# OBCv4_24.net
KiCad netlist of a schematic drawn in EAGLE
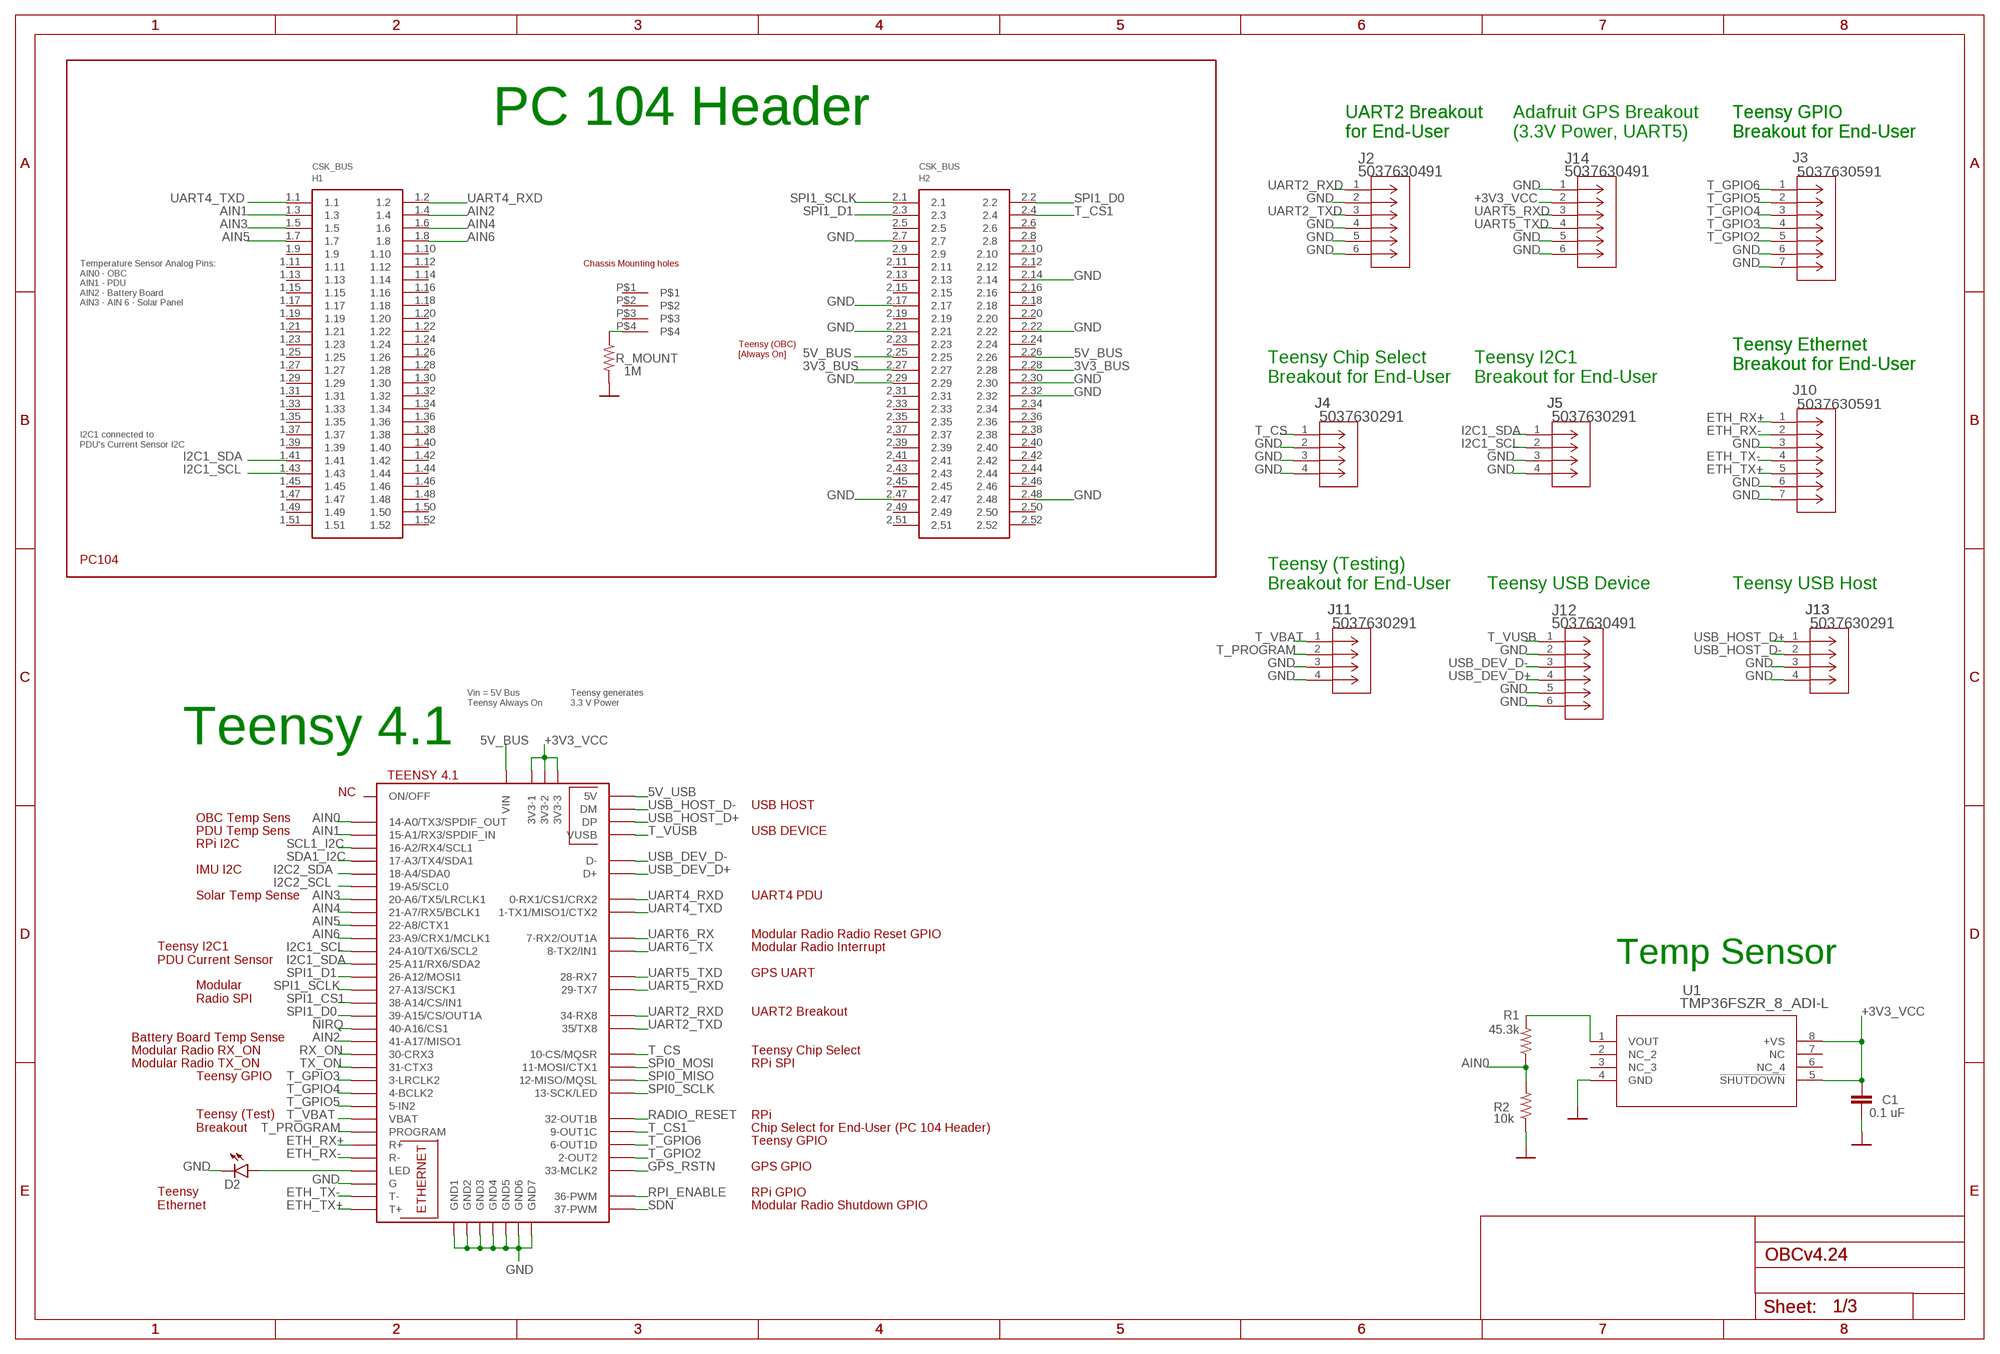
[diagram p0: schematic, sheet 1]
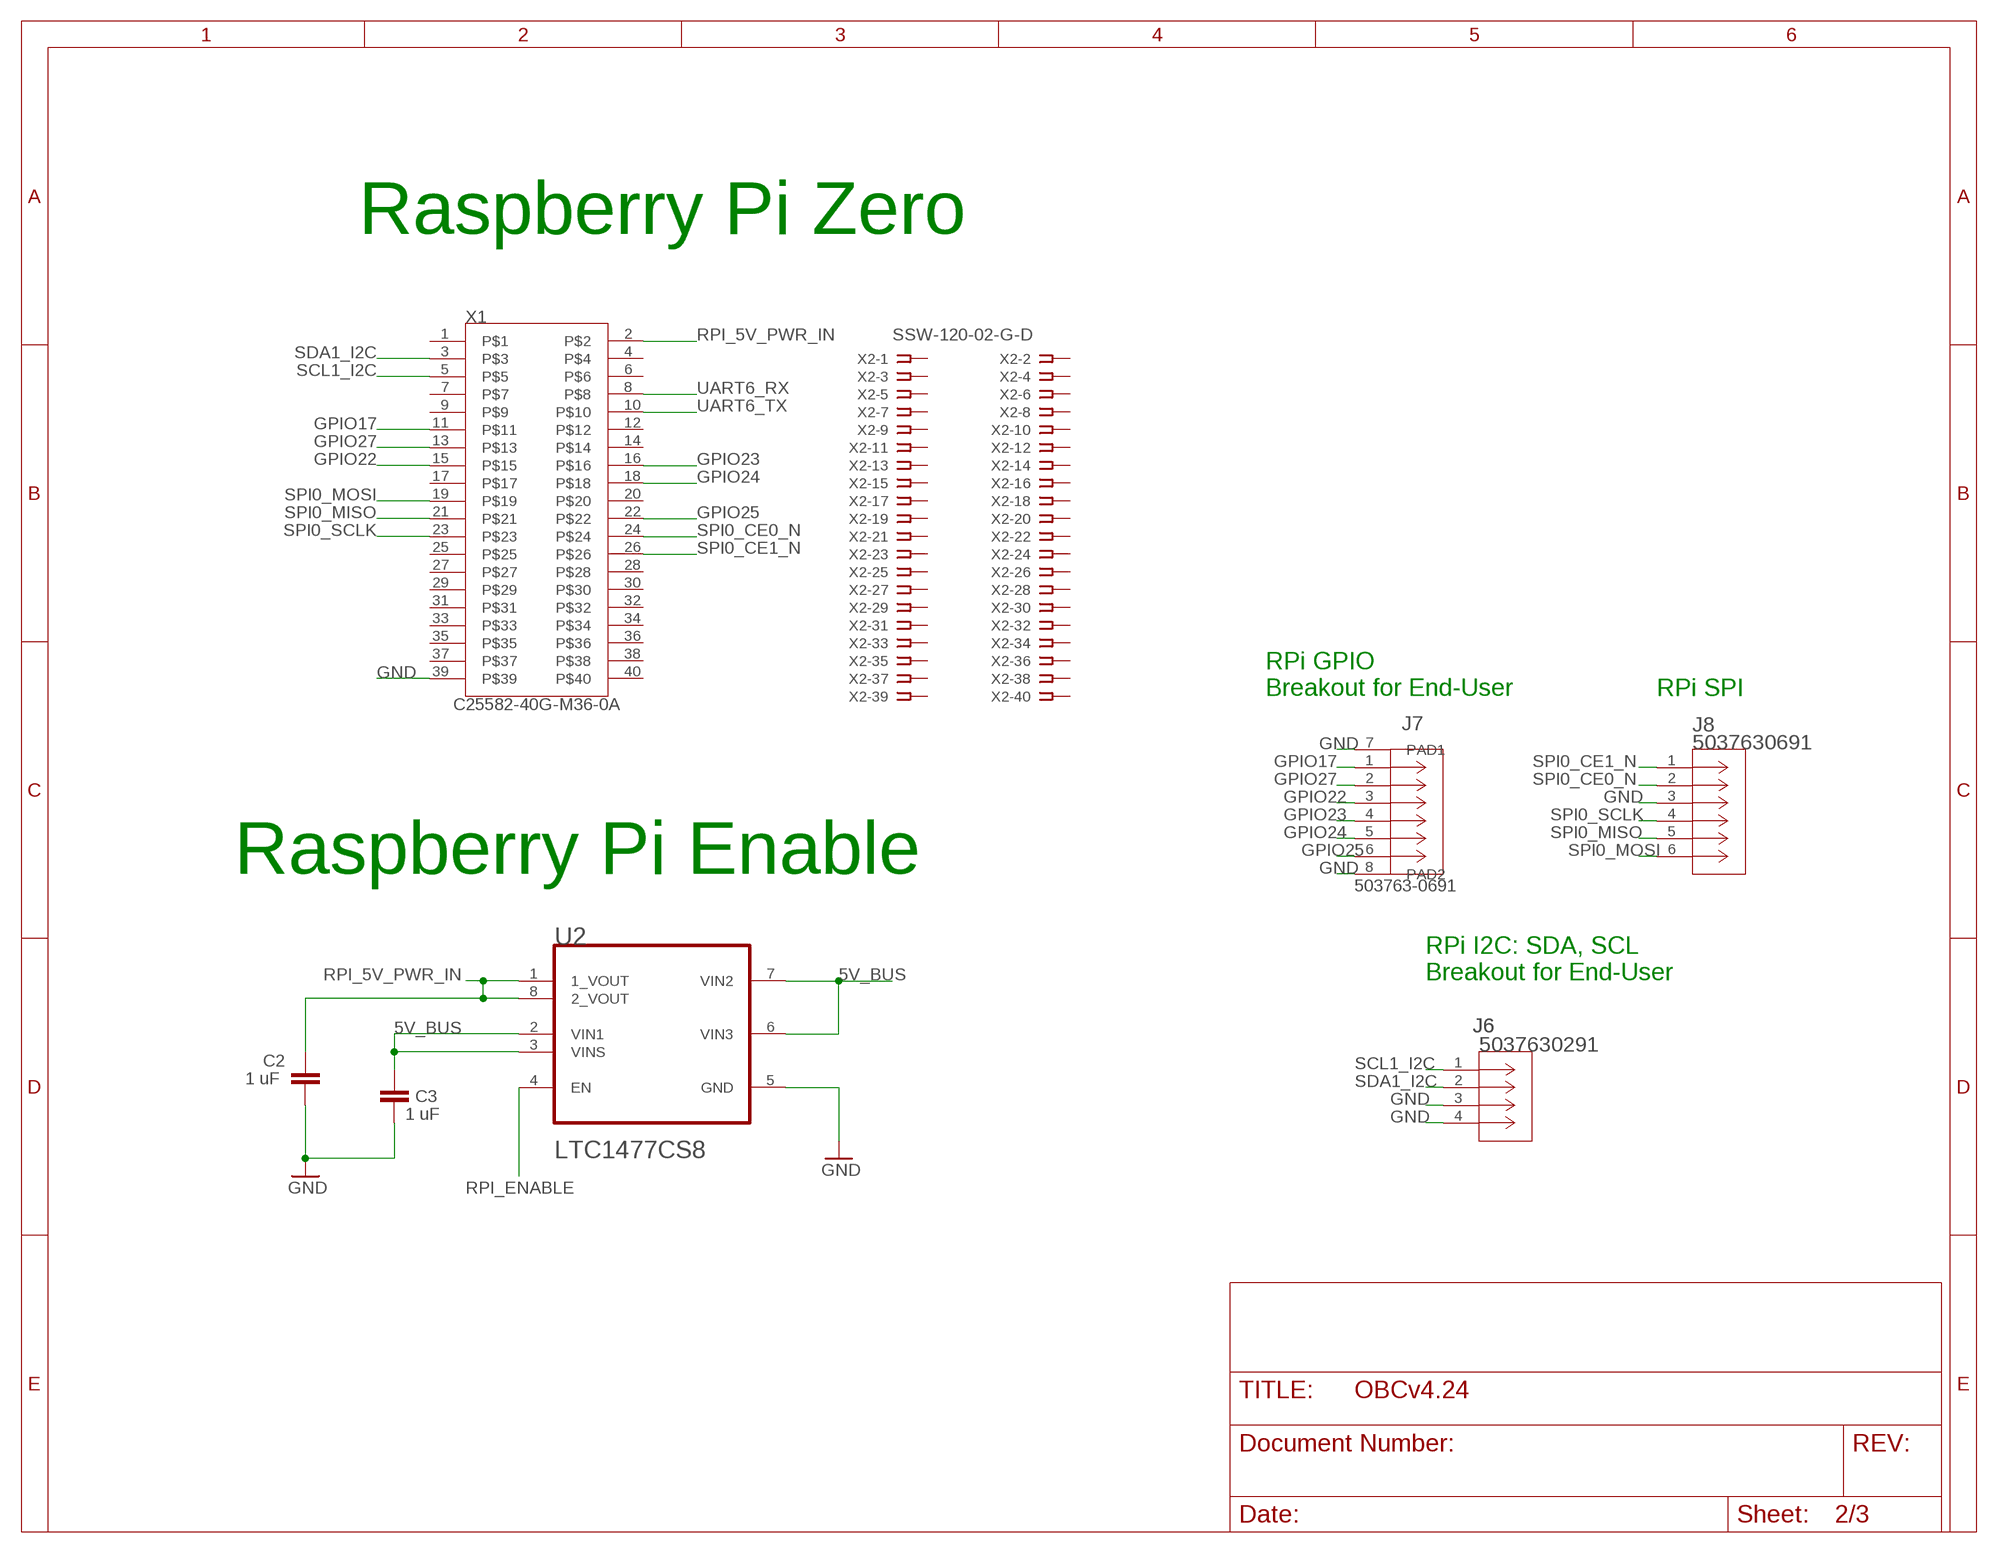
[diagram p1: schematic, sheet 2]
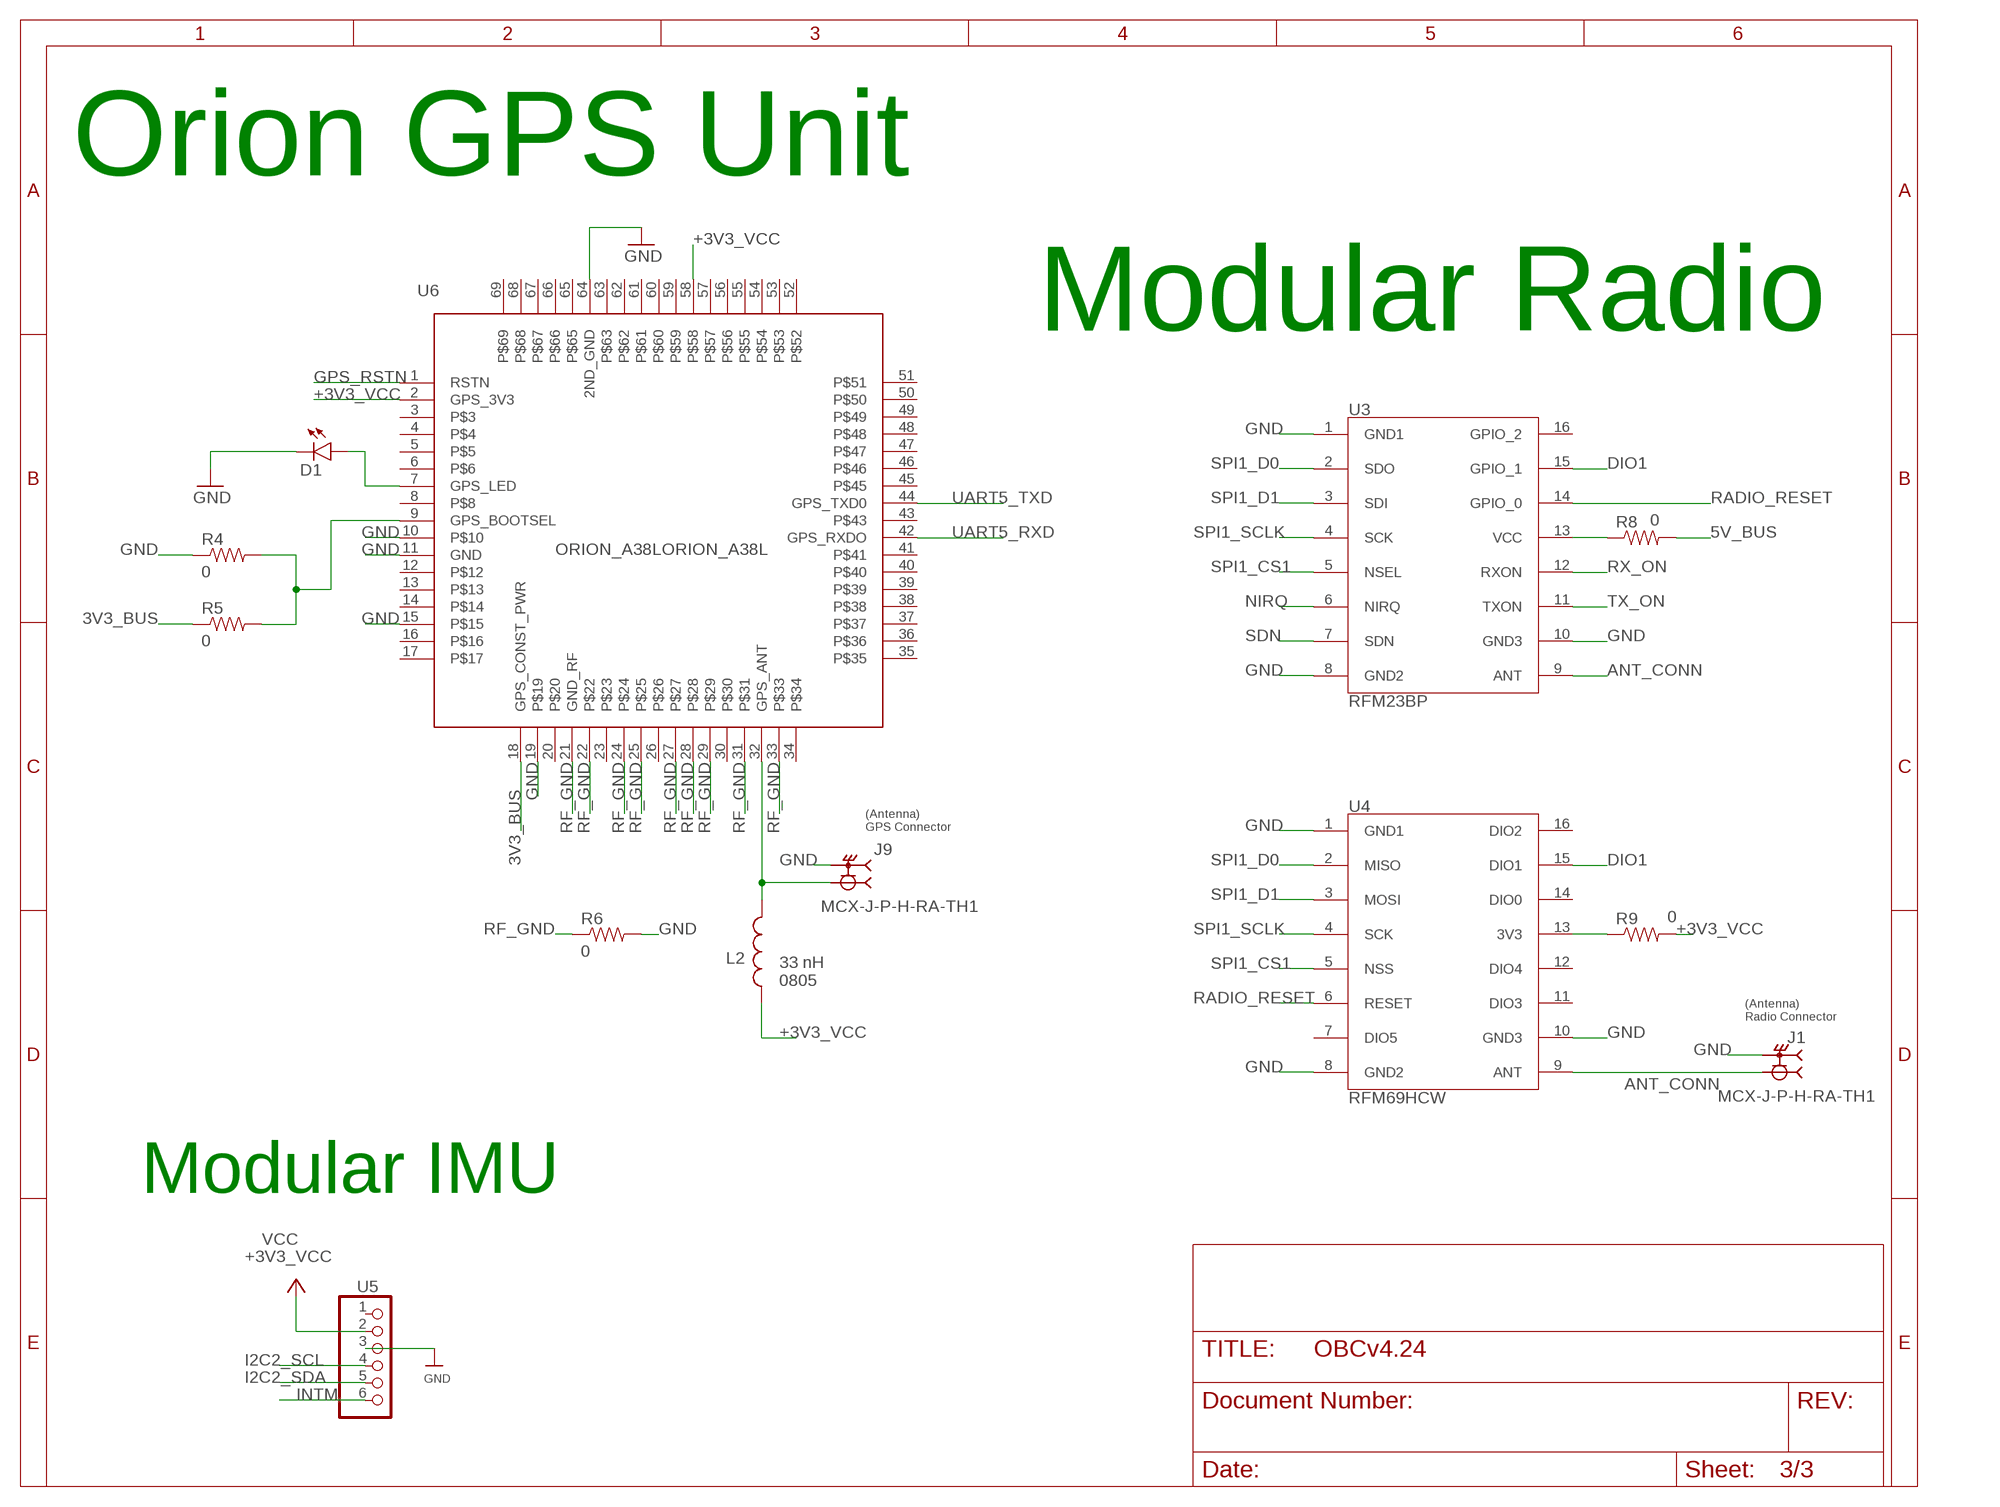
[diagram p2: schematic, sheet 3]

(export (version "E")
  (design (tool "Eeschema 10.0.6"))
  (components
    (comp (ref "C2")
      (value "1 uF")
      (footprint "eagle-import:0805")
      (libsource (lib "eagle-import") (part "CAP0805"))
    )
    (comp (ref "C3")
      (value "1 uF")
      (footprint "eagle-import:0805")
      (libsource (lib "eagle-import") (part "CAP0805"))
    )
    (comp (ref "J6")
      (value "5037630291")
      (footprint "eagle-import:CON_5037630291")
      (fields (field (name "COPYRIGHT") "Copyright (C) 2018 Accelerated Designs. All rights reserved"))
      (libsource (lib "eagle-import") (part "5037630291"))
    )
    (comp (ref "J7")
      (value "503763-0691")
      (footprint "eagle-import:CONN_503763-0691_MOL")
      (fields (field (name "COPYRIGHT") "Copyright (C) 2018 Accelerated Designs. All rights reserved"))
      (libsource (lib "eagle-import") (part "503763-0691"))
    )
    (comp (ref "J8")
      (value "5037630691")
      (footprint "eagle-import:CONN_503763-0691_MOL")
      (fields
        (field (name "MANUFACTURER_PART_NUMBER") "503763-0691")
        (field (name "COPYRIGHT") "Copyright (C) 2018 Accelerated Designs. All rights reserved")
      )
      (libsource (lib "eagle-import") (part "5037630691"))
    )
    (comp (ref "U2")
      (value "LTC1477CS8LINEAR_TECHNOLOGY_LTC1477CS8_0_2")
      (footprint "eagle-import:LINEAR_TECHNOLOGY_LTC1477CS8_2")
      (fields (field (name "MF") "Linear Technology") (field (name "MPN") "LTC1477CS8"))
      (libsource (lib "eagle-import") (part "LTC1477CS8LINEAR_TECHNOLOGY_LTC1477CS8_0_2"))
    )
    (comp (ref "X1")
      (value "C25582-40G-M36-0A")
      (footprint "eagle-import:ADAFRUIT_C25582-40G-M36-0A_0")
      (libsource (lib "eagle-import") (part "C25582-40G-M36-0A"))
    )
    (comp (ref "X2")
      (value "SSW-120-02-G-D")
      (footprint "eagle-import:SSW-120-02-G-D")
      (fields (field (name "MF") "Samtec Inc."))
      (libsource (lib "eagle-import") (part "SSW-120-02-G-D"))
    )
    (comp (ref "D1")
      (value "LEDCHIP-LED0603")
      (footprint "eagle-import:CHIP-LED0603")
      (libsource (lib "eagle-import") (part "LEDCHIP-LED0603"))
    )
    (comp (ref "J1")
      (value "MCX-J-P-H-RA-TH1")
      (footprint "eagle-import:SAMTEC_MCX-J-P-H-RA-TH1")
      (fields (field (name "DIGI-KEY_PART_NUMBER") "SAM10607-ND") (field (name "MF") "Samtec"))
      (libsource (lib "eagle-import") (part "MCX-J-P-H-RA-TH1"))
    )
    (comp (ref "J9")
      (value "MCX-J-P-H-RA-TH1")
      (footprint "eagle-import:SAMTEC_MCX-J-P-H-RA-TH1")
      (fields (field (name "DIGI-KEY_PART_NUMBER") "SAM10607-ND") (field (name "MF") "Samtec"))
      (libsource (lib "eagle-import") (part "MCX-J-P-H-RA-TH1"))
    )
    (comp (ref "L2")
      (value "AIMC-0805-2N2S-T")
      (footprint "eagle-import:INDC2012X105N")
      (fields (field (name "DIGI-KEY_PART_NUMBER") "535-11562-1-ND") (field (name "MF") "Abracon"))
      (libsource (lib "eagle-import") (part "AIMC-0805-2N2S-T"))
    )
    (comp (ref "R4")
      (value "0")
      (footprint "eagle-import:0805")
      (libsource (lib "eagle-import") (part "RESISTOR0805-RES"))
    )
    (comp (ref "R5")
      (value "0")
      (footprint "eagle-import:0805")
      (libsource (lib "eagle-import") (part "RESISTOR0805-RES"))
    )
    (comp (ref "R6")
      (value "0")
      (footprint "eagle-import:0805")
      (libsource (lib "eagle-import") (part "RESISTOR0805-RES"))
    )
    (comp (ref "R8")
      (value "0")
      (footprint "eagle-import:R2512")
      (libsource (lib "eagle-import") (part "RESISTOR2512"))
    )
    (comp (ref "R9")
      (value "0")
      (footprint "eagle-import:R2512")
      (libsource (lib "eagle-import") (part "RESISTOR2512"))
    )
    (comp (ref "U3")
      (value "RFM23BP")
      (footprint "eagle-import:RFM23BP")
      (libsource (lib "eagle-import") (part "RFM23BP"))
    )
    (comp (ref "U4")
      (value "RFM69HCW")
      (footprint "eagle-import:RFM69HCW")
      (libsource (lib "eagle-import") (part "RFM69HCW"))
    )
    (comp (ref "U5")
      (value "HEADER-1X670MIL")
      (footprint "eagle-import:1X06_ROUND_70")
      (libsource (lib "eagle-import") (part "HEADER-1X670MIL"))
    )
    (comp (ref "U6")
      (value "ORION_A38LORION_A38L")
      (footprint "eagle-import:ORION_A38L")
      (libsource (lib "eagle-import") (part "ORION_A38LORION_A38L"))
    )
    (comp (ref "C1")
      (value "0.1 uF")
      (footprint "eagle-import:0805")
      (libsource (lib "eagle-import") (part "CAP0805"))
    )
    (comp (ref "D2")
      (value "LEDCHIP-LED0603")
      (footprint "eagle-import:CHIP-LED0603")
      (libsource (lib "eagle-import") (part "LEDCHIP-LED0603"))
    )
    (comp (ref "H1")
      (value "PC104_WCONN")
      (footprint "eagle-import:PC104_WCONN")
      (libsource (lib "eagle-import") (part "PC104_WCONN"))
    )
    (comp (ref "J2")
      (value "5037630491")
      (footprint "eagle-import:CON_5037630491")
      (fields (field (name "COPYRIGHT") "Copyright (C) 2018 Accelerated Designs. All rights reserved"))
      (libsource (lib "eagle-import") (part "5037630491"))
    )
    (comp (ref "J3")
      (value "5037630591")
      (footprint "eagle-import:CON_5037630591")
      (fields (field (name "COPYRIGHT") "Copyright (C) 2021 Ultra Librarian. All rights reserved."))
      (libsource (lib "eagle-import") (part "5037630591"))
    )
    (comp (ref "J4")
      (value "5037630291")
      (footprint "eagle-import:CON_5037630291")
      (fields (field (name "COPYRIGHT") "Copyright (C) 2018 Accelerated Designs. All rights reserved"))
      (libsource (lib "eagle-import") (part "5037630291"))
    )
    (comp (ref "J5")
      (value "5037630291")
      (footprint "eagle-import:CON_5037630291")
      (fields (field (name "COPYRIGHT") "Copyright (C) 2018 Accelerated Designs. All rights reserved"))
      (libsource (lib "eagle-import") (part "5037630291"))
    )
    (comp (ref "J10")
      (value "5037630591")
      (footprint "eagle-import:CON_5037630591")
      (fields (field (name "COPYRIGHT") "Copyright (C) 2021 Ultra Librarian. All rights reserved."))
      (libsource (lib "eagle-import") (part "5037630591"))
    )
    (comp (ref "J11")
      (value "5037630291")
      (footprint "eagle-import:CON_5037630291")
      (fields (field (name "COPYRIGHT") "Copyright (C) 2018 Accelerated Designs. All rights reserved"))
      (libsource (lib "eagle-import") (part "5037630291"))
    )
    (comp (ref "J12")
      (value "5037630491")
      (footprint "eagle-import:CON_5037630491")
      (fields (field (name "COPYRIGHT") "Copyright (C) 2018 Accelerated Designs. All rights reserved"))
      (libsource (lib "eagle-import") (part "5037630491"))
    )
    (comp (ref "J13")
      (value "5037630291")
      (footprint "eagle-import:CON_5037630291")
      (fields (field (name "COPYRIGHT") "Copyright (C) 2018 Accelerated Designs. All rights reserved"))
      (libsource (lib "eagle-import") (part "5037630291"))
    )
    (comp (ref "J14")
      (value "5037630491")
      (footprint "eagle-import:CON_5037630491")
      (fields (field (name "COPYRIGHT") "Copyright (C) 2018 Accelerated Designs. All rights reserved"))
      (libsource (lib "eagle-import") (part "5037630491"))
    )
    (comp (ref "R1")
      (value "45.3k")
      (footprint "eagle-import:0805")
      (libsource (lib "eagle-import") (part "RESISTOR0805-RES"))
    )
    (comp (ref "R2")
      (value "10k")
      (footprint "eagle-import:0805")
      (libsource (lib "eagle-import") (part "RESISTOR0805-RES"))
    )
    (comp (ref "R_MOUNT")
      (value "1M")
      (footprint "eagle-import:0805")
      (libsource (lib "eagle-import") (part "RESISTOR0805-RES"))
    )
    (comp (ref "U$1")
      (value "TEENSY41TEENSY")
      (footprint "eagle-import:TEENSY41")
      (libsource (lib "eagle-import") (part "TEENSY41TEENSY"))
    )
    (comp (ref "U1")
      (value "TMP36FSZR_8_ADI-L")
      (footprint "eagle-import:R_8_ADI-L")
      (fields
        (field (name "MANUFACTURER_PART_NUMBER") "TMP36FSZ")
        (field (name "COPYRIGHT") "Copyright (C) 2021 Ultra Librarian. All rights reserved.")
      )
      (libsource (lib "eagle-import") (part "TMP36FSZR_8_ADI-L"))
    )
  )
  (nets
    (net (code "1") (name "+3V3_VCC") (class "Default")
      (node (ref "C1") (pin "1") (pinfunction "1_1") (pintype "passive"))
      (node (ref "J14") (pin "2") (pinfunction "2_2") (pintype "passive"))
      (node (ref "L2") (pin "1") (pinfunction "1_1") (pintype "passive"))
      (node (ref "R9") (pin "2") (pinfunction "2_2") (pintype "passive"))
      (node (ref "U$1") (pin "3V3-1") (pinfunction "3V3-1_3V3-1") (pintype "bidirectional"))
      (node (ref "U$1") (pin "3V3-2") (pinfunction "3V3-2_3V3-2") (pintype "bidirectional"))
      (node (ref "U$1") (pin "3V3-3") (pinfunction "3V3-3_3V3-3") (pintype "bidirectional"))
      (node (ref "U1") (pin "5") (pinfunction "~{SHUTDOWN}_5") (pintype "passive"))
      (node (ref "U1") (pin "8") (pinfunction "+VS_8") (pintype "power_in"))
      (node (ref "U5") (pin "2") (pinfunction "2_2") (pintype "passive"))
      (node (ref "U6") (pin "2") (pinfunction "GPS_3V3_2") (pintype "bidirectional"))
      (node (ref "U6") (pin "58") (pinfunction "P$58_58") (pintype "bidirectional"))
    )
    (net (code "2") (name "3V3_BUS") (class "Default")
      (node (ref "H1") (pin "2.27") (pinfunction "2.27_2.27") (pintype "bidirectional"))
      (node (ref "H1") (pin "2.28") (pinfunction "2.28_2.28") (pintype "bidirectional"))
      (node (ref "R5") (pin "1") (pinfunction "1_1") (pintype "passive"))
      (node (ref "U6") (pin "18") (pinfunction "GPS_CONST_PWR_18") (pintype "bidirectional"))
    )
    (net (code "3") (name "5V_BUS") (class "Default")
      (node (ref "C3") (pin "1") (pinfunction "1_1") (pintype "passive"))
      (node (ref "H1") (pin "2.25") (pinfunction "2.25_2.25") (pintype "bidirectional"))
      (node (ref "H1") (pin "2.26") (pinfunction "2.26_2.26") (pintype "bidirectional"))
      (node (ref "R8") (pin "2") (pinfunction "2_2") (pintype "passive"))
      (node (ref "U$1") (pin "VIN") (pinfunction "VIN_VIN") (pintype "bidirectional"))
      (node (ref "U2") (pin "2") (pinfunction "VIN1_2") (pintype "power_in"))
      (node (ref "U2") (pin "3") (pinfunction "VINS_3") (pintype "power_in"))
      (node (ref "U2") (pin "6") (pinfunction "VIN3_6") (pintype "power_in"))
      (node (ref "U2") (pin "7") (pinfunction "VIN2_7") (pintype "power_in"))
    )
    (net (code "4") (name "5V_USB") (class "Default")
      (node (ref "U$1") (pin "+5V") (pinfunction "5V_+5V") (pintype "bidirectional"))
    )
    (net (code "5") (name "AIN0") (class "Default")
      (node (ref "R1") (pin "1") (pinfunction "1_1") (pintype "passive"))
      (node (ref "R2") (pin "2") (pinfunction "2_2") (pintype "passive"))
      (node (ref "U$1") (pin "14-A0/TX3/SPDIF_OUT") (pinfunction "14-A0/TX3/SPDIF_OUT_14-A0/TX3/SPDIF_OUT") (pintype "bidirectional"))
    )
    (net (code "6") (name "AIN1") (class "Default")
      (node (ref "H1") (pin "1.3") (pinfunction "1.3_1.3") (pintype "bidirectional"))
      (node (ref "U$1") (pin "15-A1/RX3/SPDIF_IN") (pinfunction "15-A1/RX3/SPDIF_IN_15-A1/RX3/SPDIF_IN") (pintype "bidirectional"))
    )
    (net (code "7") (name "AIN2") (class "Default")
      (node (ref "H1") (pin "1.4") (pinfunction "1.4_1.4") (pintype "bidirectional"))
      (node (ref "U$1") (pin "41-A17/MISO1") (pinfunction "41-A17/MISO1_41-A17/MISO1") (pintype "bidirectional"))
    )
    (net (code "8") (name "AIN3") (class "Default")
      (node (ref "H1") (pin "1.5") (pinfunction "1.5_1.5") (pintype "bidirectional"))
      (node (ref "U$1") (pin "20-A6/TX5/LRCLK1") (pinfunction "20-A6/TX5/LRCLK1_20-A6/TX5/LRCLK1") (pintype "bidirectional"))
    )
    (net (code "9") (name "AIN4") (class "Default")
      (node (ref "H1") (pin "1.6") (pinfunction "1.6_1.6") (pintype "bidirectional"))
      (node (ref "U$1") (pin "21-A7/RX5/BCLK1") (pinfunction "21-A7/RX5/BCLK1_21-A7/RX5/BCLK1") (pintype "bidirectional"))
    )
    (net (code "10") (name "AIN5") (class "Default")
      (node (ref "H1") (pin "1.7") (pinfunction "1.7_1.7") (pintype "bidirectional"))
      (node (ref "U$1") (pin "22-A8/CTX1") (pinfunction "22-A8/CTX1_22-A8/CTX1") (pintype "bidirectional"))
    )
    (net (code "11") (name "AIN6") (class "Default")
      (node (ref "H1") (pin "1.8") (pinfunction "1.8_1.8") (pintype "bidirectional"))
      (node (ref "U$1") (pin "23-A9/CRX1/MCLK1") (pinfunction "23-A9/CRX1/MCLK1_23-A9/CRX1/MCLK1") (pintype "bidirectional"))
    )
    (net (code "12") (name "ANT_CONN") (class "Default")
      (node (ref "J1") (pin "1") (pinfunction "1_1") (pintype "passive"))
      (node (ref "U3") (pin "9") (pinfunction "ANT_9") (pintype "bidirectional"))
      (node (ref "U4") (pin "9") (pinfunction "ANT_9") (pintype "bidirectional"))
    )
    (net (code "13") (name "DIO1") (class "Default")
      (node (ref "U3") (pin "15") (pinfunction "GPIO_1_15") (pintype "bidirectional"))
      (node (ref "U4") (pin "15") (pinfunction "DIO1_15") (pintype "bidirectional"))
    )
    (net (code "14") (name "ETH_RX+") (class "Default")
      (node (ref "J10") (pin "1") (pinfunction "1_1") (pintype "passive"))
      (node (ref "U$1") (pin "R+") (pinfunction "R+_R+") (pintype "bidirectional"))
    )
    (net (code "15") (name "ETH_RX-") (class "Default")
      (node (ref "J10") (pin "2") (pinfunction "2_2") (pintype "passive"))
      (node (ref "U$1") (pin "R-") (pinfunction "R-_R-") (pintype "bidirectional"))
    )
    (net (code "16") (name "ETH_TX+") (class "Default")
      (node (ref "J10") (pin "5") (pinfunction "5_5") (pintype "passive"))
      (node (ref "U$1") (pin "T+") (pinfunction "T+_T+") (pintype "bidirectional"))
    )
    (net (code "17") (name "ETH_TX-") (class "Default")
      (node (ref "J10") (pin "4") (pinfunction "4_4") (pintype "passive"))
      (node (ref "U$1") (pin "T-") (pinfunction "T-_T-") (pintype "bidirectional"))
    )
    (net (code "18") (name "GND") (class "Default")
      (node (ref "C1") (pin "2") (pinfunction "2_2") (pintype "passive"))
      (node (ref "C2") (pin "2") (pinfunction "2_2") (pintype "passive"))
      (node (ref "C3") (pin "2") (pinfunction "2_2") (pintype "passive"))
      (node (ref "D1") (pin "C") (pinfunction "C_C") (pintype "passive"))
      (node (ref "D2") (pin "C") (pinfunction "C_C") (pintype "passive"))
      (node (ref "H1") (pin "2.14") (pinfunction "2.14_2.14") (pintype "bidirectional"))
      (node (ref "H1") (pin "2.17") (pinfunction "2.17_2.17") (pintype "bidirectional"))
      (node (ref "H1") (pin "2.21") (pinfunction "2.21_2.21") (pintype "bidirectional"))
      (node (ref "H1") (pin "2.22") (pinfunction "2.22_2.22") (pintype "bidirectional"))
      (node (ref "H1") (pin "2.29") (pinfunction "2.29_2.29") (pintype "bidirectional"))
      (node (ref "H1") (pin "2.30") (pinfunction "2.30_2.30") (pintype "bidirectional"))
      (node (ref "H1") (pin "2.32") (pinfunction "2.32_2.32") (pintype "bidirectional"))
      (node (ref "H1") (pin "2.47") (pinfunction "2.47_2.47") (pintype "bidirectional"))
      (node (ref "H1") (pin "2.48") (pinfunction "2.48_2.48") (pintype "bidirectional"))
      (node (ref "H1") (pin "2.7") (pinfunction "2.7_2.7") (pintype "bidirectional"))
      (node (ref "J1") (pin "S1") (pinfunction "2_S1") (pintype "passive"))
      (node (ref "J1") (pin "S2") (pinfunction "2_S2") (pintype "passive"))
      (node (ref "J1") (pin "S3") (pinfunction "2_S3") (pintype "passive"))
      (node (ref "J1") (pin "S4") (pinfunction "2_S4") (pintype "passive"))
      (node (ref "J10") (pin "3") (pinfunction "3_3") (pintype "passive"))
      (node (ref "J10") (pin "6") (pinfunction "6_6") (pintype "passive"))
      (node (ref "J10") (pin "7") (pinfunction "7_7") (pintype "passive"))
      (node (ref "J11") (pin "3") (pinfunction "3_3") (pintype "passive"))
      (node (ref "J11") (pin "4") (pinfunction "4_4") (pintype "passive"))
      (node (ref "J12") (pin "2") (pinfunction "2_2") (pintype "passive"))
      (node (ref "J12") (pin "5") (pinfunction "5_5") (pintype "passive"))
      (node (ref "J12") (pin "6") (pinfunction "6_6") (pintype "passive"))
      (node (ref "J13") (pin "3") (pinfunction "3_3") (pintype "passive"))
      (node (ref "J13") (pin "4") (pinfunction "4_4") (pintype "passive"))
      (node (ref "J14") (pin "1") (pinfunction "1_1") (pintype "passive"))
      (node (ref "J14") (pin "5") (pinfunction "5_5") (pintype "passive"))
      (node (ref "J14") (pin "6") (pinfunction "6_6") (pintype "passive"))
      (node (ref "J2") (pin "2") (pinfunction "2_2") (pintype "passive"))
      (node (ref "J2") (pin "4") (pinfunction "4_4") (pintype "passive"))
      (node (ref "J2") (pin "5") (pinfunction "5_5") (pintype "passive"))
      (node (ref "J2") (pin "6") (pinfunction "6_6") (pintype "passive"))
      (node (ref "J3") (pin "6") (pinfunction "6_6") (pintype "passive"))
      (node (ref "J3") (pin "7") (pinfunction "7_7") (pintype "passive"))
      (node (ref "J4") (pin "2") (pinfunction "2_2") (pintype "passive"))
      (node (ref "J4") (pin "3") (pinfunction "3_3") (pintype "passive"))
      (node (ref "J4") (pin "4") (pinfunction "4_4") (pintype "passive"))
      (node (ref "J5") (pin "3") (pinfunction "3_3") (pintype "passive"))
      (node (ref "J5") (pin "4") (pinfunction "4_4") (pintype "passive"))
      (node (ref "J6") (pin "3") (pinfunction "3_3") (pintype "passive"))
      (node (ref "J6") (pin "4") (pinfunction "4_4") (pintype "passive"))
      (node (ref "J7") (pin "7") (pinfunction "PAD1_7") (pintype "bidirectional"))
      (node (ref "J7") (pin "8") (pinfunction "PAD2_8") (pintype "bidirectional"))
      (node (ref "J8") (pin "3") (pinfunction "3_3") (pintype "passive"))
      (node (ref "J9") (pin "S1") (pinfunction "2_S1") (pintype "passive"))
      (node (ref "J9") (pin "S2") (pinfunction "2_S2") (pintype "passive"))
      (node (ref "J9") (pin "S3") (pinfunction "2_S3") (pintype "passive"))
      (node (ref "J9") (pin "S4") (pinfunction "2_S4") (pintype "passive"))
      (node (ref "R2") (pin "1") (pinfunction "1_1") (pintype "passive"))
      (node (ref "R4") (pin "1") (pinfunction "1_1") (pintype "passive"))
      (node (ref "R6") (pin "2") (pinfunction "2_2") (pintype "passive"))
      (node (ref "R_MOUNT") (pin "2") (pinfunction "2_2") (pintype "passive"))
      (node (ref "U$1") (pin "G") (pinfunction "G_G") (pintype "bidirectional"))
      (node (ref "U$1") (pin "GND") (pinfunction "GND7_GND") (pintype "bidirectional"))
      (node (ref "U$1") (pin "GND1") (pinfunction "GND1_GND1") (pintype "bidirectional"))
      (node (ref "U$1") (pin "GND2") (pinfunction "GND2_GND2") (pintype "bidirectional"))
      (node (ref "U$1") (pin "GND3") (pinfunction "GND3_GND3") (pintype "bidirectional"))
      (node (ref "U$1") (pin "GND4") (pinfunction "GND4_GND4") (pintype "bidirectional"))
      (node (ref "U$1") (pin "GND5") (pinfunction "GND5_GND5") (pintype "bidirectional"))
      (node (ref "U$1") (pin "GND6") (pinfunction "GND6_GND6") (pintype "bidirectional"))
      (node (ref "U1") (pin "4") (pinfunction "GND_4") (pintype "passive"))
      (node (ref "U2") (pin "5") (pinfunction "GND_5") (pintype "power_in"))
      (node (ref "U3") (pin "1") (pinfunction "GND1_1") (pintype "bidirectional"))
      (node (ref "U3") (pin "10") (pinfunction "GND3_10") (pintype "bidirectional"))
      (node (ref "U3") (pin "8") (pinfunction "GND2_8") (pintype "bidirectional"))
      (node (ref "U4") (pin "1") (pinfunction "GND1_1") (pintype "bidirectional"))
      (node (ref "U4") (pin "10") (pinfunction "GND3_10") (pintype "bidirectional"))
      (node (ref "U4") (pin "8") (pinfunction "GND2_8") (pintype "bidirectional"))
      (node (ref "U5") (pin "3") (pinfunction "3_3") (pintype "passive"))
      (node (ref "U6") (pin "10") (pinfunction "P$10_10") (pintype "bidirectional"))
      (node (ref "U6") (pin "11") (pinfunction "GND_11") (pintype "bidirectional"))
      (node (ref "U6") (pin "15") (pinfunction "P$15_15") (pintype "bidirectional"))
      (node (ref "U6") (pin "19") (pinfunction "P$19_19") (pintype "bidirectional"))
      (node (ref "U6") (pin "64") (pinfunction "2ND_GND_64") (pintype "bidirectional"))
      (node (ref "X1") (pin "39") (pinfunction "P$39_39") (pintype "bidirectional"))
    )
    (net (code "19") (name "GPIO17") (class "Default")
      (node (ref "J7") (pin "1") (pinfunction "1_1") (pintype "passive"))
      (node (ref "X1") (pin "11") (pinfunction "P$11_11") (pintype "bidirectional"))
    )
    (net (code "20") (name "GPIO22") (class "Default")
      (node (ref "J7") (pin "3") (pinfunction "3_3") (pintype "passive"))
      (node (ref "X1") (pin "15") (pinfunction "P$15_15") (pintype "bidirectional"))
    )
    (net (code "21") (name "GPIO23") (class "Default")
      (node (ref "J7") (pin "4") (pinfunction "4_4") (pintype "passive"))
      (node (ref "X1") (pin "16") (pinfunction "P$16_16") (pintype "bidirectional"))
    )
    (net (code "22") (name "GPIO24") (class "Default")
      (node (ref "J7") (pin "5") (pinfunction "5_5") (pintype "passive"))
      (node (ref "X1") (pin "18") (pinfunction "P$18_18") (pintype "bidirectional"))
    )
    (net (code "23") (name "GPIO25") (class "Default")
      (node (ref "J7") (pin "6") (pinfunction "6_6") (pintype "passive"))
      (node (ref "X1") (pin "22") (pinfunction "P$22_22") (pintype "bidirectional"))
    )
    (net (code "24") (name "GPIO27") (class "Default")
      (node (ref "J7") (pin "2") (pinfunction "2_2") (pintype "passive"))
      (node (ref "X1") (pin "13") (pinfunction "P$13_13") (pintype "bidirectional"))
    )
    (net (code "25") (name "GPS_RSTN") (class "Default")
      (node (ref "U$1") (pin "33-MCLK2") (pinfunction "33-MCLK2_33-MCLK2") (pintype "bidirectional"))
      (node (ref "U6") (pin "1") (pinfunction "RSTN_1") (pintype "bidirectional"))
    )
    (net (code "26") (name "I2C1_SCL") (class "Default")
      (node (ref "H1") (pin "1.43") (pinfunction "1.43_1.43") (pintype "bidirectional"))
      (node (ref "J5") (pin "2") (pinfunction "2_2") (pintype "passive"))
      (node (ref "U$1") (pin "24-A10/TX6/SCL2") (pinfunction "24-A10/TX6/SCL2_24-A10/TX6/SCL2") (pintype "bidirectional"))
    )
    (net (code "27") (name "I2C1_SDA") (class "Default")
      (node (ref "H1") (pin "1.41") (pinfunction "1.41_1.41") (pintype "bidirectional"))
      (node (ref "J5") (pin "1") (pinfunction "1_1") (pintype "passive"))
      (node (ref "U$1") (pin "25-A11/RX6/SDA2") (pinfunction "25-A11/RX6/SDA2_25-A11/RX6/SDA2") (pintype "bidirectional"))
    )
    (net (code "28") (name "I2C2_SCL") (class "Default")
      (node (ref "U$1") (pin "19-A5/SCL0") (pinfunction "19-A5/SCL0_19-A5/SCL0") (pintype "bidirectional"))
      (node (ref "U5") (pin "4") (pinfunction "4_4") (pintype "passive"))
    )
    (net (code "29") (name "I2C2_SDA") (class "Default")
      (node (ref "U$1") (pin "18-A4/SDA0") (pinfunction "18-A4/SDA0_18-A4/SDA0") (pintype "bidirectional"))
      (node (ref "U5") (pin "5") (pinfunction "5_5") (pintype "passive"))
    )
    (net (code "30") (name "INTM") (class "Default")
      (node (ref "U5") (pin "6") (pinfunction "6_6") (pintype "passive"))
    )
    (net (code "31") (name "NIRQ") (class "Default")
      (node (ref "U$1") (pin "40-A16/CS1") (pinfunction "40-A16/CS1_40-A16/CS1") (pintype "bidirectional"))
      (node (ref "U3") (pin "6") (pinfunction "NIRQ_6") (pintype "bidirectional"))
    )
    (net (code "32") (name "Net-(D2-PadA)") (class "Default")
      (node (ref "D2") (pin "A") (pinfunction "A_A") (pintype "passive"))
      (node (ref "U$1") (pin "LED") (pinfunction "LED_LED") (pintype "bidirectional"))
    )
    (net (code "33") (name "Net-(H1-PadP$4)") (class "Default")
      (node (ref "H1") (pin "P$4") (pinfunction "P$4_P$4") (pintype "bidirectional"))
      (node (ref "R_MOUNT") (pin "1") (pinfunction "1_1") (pintype "passive"))
    )
    (net (code "34") (name "Net-(U1-VOUT)") (class "Default")
      (node (ref "R1") (pin "2") (pinfunction "2_2") (pintype "passive"))
      (node (ref "U1") (pin "1") (pinfunction "VOUT_1") (pintype "output"))
    )
    (net (code "35") (name "Net-(U3-VCC)") (class "Default")
      (node (ref "R8") (pin "1") (pinfunction "1_1") (pintype "passive"))
      (node (ref "U3") (pin "13") (pinfunction "VCC_13") (pintype "bidirectional"))
    )
    (net (code "36") (name "Net-(U4-3V3)") (class "Default")
      (node (ref "R9") (pin "1") (pinfunction "1_1") (pintype "passive"))
      (node (ref "U4") (pin "13") (pinfunction "3V3_13") (pintype "bidirectional"))
    )
    (net (code "37") (name "Net-(U6-GPS_ANT)") (class "Default")
      (node (ref "J9") (pin "1") (pinfunction "1_1") (pintype "passive"))
      (node (ref "L2") (pin "2") (pinfunction "2_2") (pintype "passive"))
      (node (ref "U6") (pin "32") (pinfunction "GPS_ANT_32") (pintype "bidirectional"))
    )
    (net (code "38") (name "Net-(U6-GPS_BOOTSEL)") (class "Default")
      (node (ref "R4") (pin "2") (pinfunction "2_2") (pintype "passive"))
      (node (ref "R5") (pin "2") (pinfunction "2_2") (pintype "passive"))
      (node (ref "U6") (pin "9") (pinfunction "GPS_BOOTSEL_9") (pintype "bidirectional"))
    )
    (net (code "39") (name "Net-(U6-GPS_LED)") (class "Default")
      (node (ref "D1") (pin "A") (pinfunction "A_A") (pintype "passive"))
      (node (ref "U6") (pin "7") (pinfunction "GPS_LED_7") (pintype "bidirectional"))
    )
    (net (code "40") (name "RADIO_RESET") (class "Default")
      (node (ref "U$1") (pin "32-OUT1B") (pinfunction "32-OUT1B_32-OUT1B") (pintype "bidirectional"))
      (node (ref "U3") (pin "14") (pinfunction "GPIO_0_14") (pintype "bidirectional"))
      (node (ref "U4") (pin "6") (pinfunction "RESET_6") (pintype "bidirectional"))
    )
    (net (code "41") (name "RF_GND") (class "Default")
      (node (ref "R6") (pin "1") (pinfunction "1_1") (pintype "passive"))
      (node (ref "U6") (pin "21") (pinfunction "GND_RF_21") (pintype "bidirectional"))
      (node (ref "U6") (pin "22") (pinfunction "P$22_22") (pintype "bidirectional"))
      (node (ref "U6") (pin "24") (pinfunction "P$24_24") (pintype "bidirectional"))
      (node (ref "U6") (pin "25") (pinfunction "P$25_25") (pintype "bidirectional"))
      (node (ref "U6") (pin "27") (pinfunction "P$27_27") (pintype "bidirectional"))
      (node (ref "U6") (pin "28") (pinfunction "P$28_28") (pintype "bidirectional"))
      (node (ref "U6") (pin "29") (pinfunction "P$29_29") (pintype "bidirectional"))
      (node (ref "U6") (pin "31") (pinfunction "P$31_31") (pintype "bidirectional"))
      (node (ref "U6") (pin "33") (pinfunction "P$33_33") (pintype "bidirectional"))
    )
    (net (code "42") (name "RPI_5V_PWR_IN") (class "Default")
      (node (ref "C2") (pin "1") (pinfunction "1_1") (pintype "passive"))
      (node (ref "U2") (pin "1") (pinfunction "1_VOUT_1") (pintype "power_in"))
      (node (ref "U2") (pin "8") (pinfunction "2_VOUT_8") (pintype "power_in"))
      (node (ref "X1") (pin "2") (pinfunction "P$2_2") (pintype "bidirectional"))
    )
    (net (code "43") (name "RPI_ENABLE") (class "Default")
      (node (ref "U$1") (pin "36-PWM") (pinfunction "36-PWM_36-PWM") (pintype "bidirectional"))
      (node (ref "U2") (pin "4") (pinfunction "EN_4") (pintype "input"))
    )
    (net (code "44") (name "RX_ON") (class "Default")
      (node (ref "U$1") (pin "30-CRX3") (pinfunction "30-CRX3_30-CRX3") (pintype "bidirectional"))
      (node (ref "U3") (pin "12") (pinfunction "RXON_12") (pintype "bidirectional"))
    )
    (net (code "45") (name "SCL1_I2C") (class "Default")
      (node (ref "J6") (pin "1") (pinfunction "1_1") (pintype "passive"))
      (node (ref "U$1") (pin "16-A2/RX4/SCL1") (pinfunction "16-A2/RX4/SCL1_16-A2/RX4/SCL1") (pintype "bidirectional"))
      (node (ref "X1") (pin "5") (pinfunction "P$5_5") (pintype "bidirectional"))
    )
    (net (code "46") (name "SDA1_I2C") (class "Default")
      (node (ref "J6") (pin "2") (pinfunction "2_2") (pintype "passive"))
      (node (ref "U$1") (pin "17-A3/TX4/SDA1") (pinfunction "17-A3/TX4/SDA1_17-A3/TX4/SDA1") (pintype "bidirectional"))
      (node (ref "X1") (pin "3") (pinfunction "P$3_3") (pintype "bidirectional"))
    )
    (net (code "47") (name "SDN") (class "Default")
      (node (ref "U$1") (pin "37-PWM") (pinfunction "37-PWM_37-PWM") (pintype "bidirectional"))
      (node (ref "U3") (pin "7") (pinfunction "SDN_7") (pintype "bidirectional"))
    )
    (net (code "48") (name "SPI0_CE0_N") (class "Default")
      (node (ref "J8") (pin "2") (pinfunction "2_2") (pintype "passive"))
      (node (ref "X1") (pin "24") (pinfunction "P$24_24") (pintype "bidirectional"))
    )
    (net (code "49") (name "SPI0_CE1_N") (class "Default")
      (node (ref "J8") (pin "1") (pinfunction "1_1") (pintype "passive"))
      (node (ref "X1") (pin "26") (pinfunction "P$26_26") (pintype "bidirectional"))
    )
    (net (code "50") (name "SPI0_MISO") (class "Default")
      (node (ref "J8") (pin "5") (pinfunction "5_5") (pintype "passive"))
      (node (ref "U$1") (pin "12-MISO/MQSL") (pinfunction "12-MISO/MQSL_12-MISO/MQSL") (pintype "bidirectional"))
      (node (ref "X1") (pin "21") (pinfunction "P$21_21") (pintype "bidirectional"))
    )
    (net (code "51") (name "SPI0_MOSI") (class "Default")
      (node (ref "J8") (pin "6") (pinfunction "6_6") (pintype "passive"))
      (node (ref "U$1") (pin "11-MOSI/CTX1") (pinfunction "11-MOSI/CTX1_11-MOSI/CTX1") (pintype "bidirectional"))
      (node (ref "X1") (pin "19") (pinfunction "P$19_19") (pintype "bidirectional"))
    )
    (net (code "52") (name "SPI0_SCLK") (class "Default")
      (node (ref "J8") (pin "4") (pinfunction "4_4") (pintype "passive"))
      (node (ref "U$1") (pin "13-SCK/LED") (pinfunction "13-SCK/LED_13-SCK/LED") (pintype "bidirectional"))
      (node (ref "X1") (pin "23") (pinfunction "P$23_23") (pintype "bidirectional"))
    )
    (net (code "53") (name "SPI1_CS1") (class "Default")
      (node (ref "U$1") (pin "38-A14/CS/IN1") (pinfunction "38-A14/CS/IN1_38-A14/CS/IN1") (pintype "bidirectional"))
      (node (ref "U3") (pin "5") (pinfunction "NSEL_5") (pintype "bidirectional"))
      (node (ref "U4") (pin "5") (pinfunction "NSS_5") (pintype "bidirectional"))
    )
    (net (code "54") (name "SPI1_D0") (class "Default")
      (node (ref "H1") (pin "2.2") (pinfunction "2.2_2.2") (pintype "bidirectional"))
      (node (ref "U$1") (pin "39-A15/CS/OUT1A") (pinfunction "39-A15/CS/OUT1A_39-A15/CS/OUT1A") (pintype "bidirectional"))
      (node (ref "U3") (pin "2") (pinfunction "SDO_2") (pintype "bidirectional"))
      (node (ref "U4") (pin "2") (pinfunction "MISO_2") (pintype "bidirectional"))
    )
    (net (code "55") (name "SPI1_D1") (class "Default")
      (node (ref "H1") (pin "2.3") (pinfunction "2.3_2.3") (pintype "bidirectional"))
      (node (ref "U$1") (pin "26-A12/MOSI1") (pinfunction "26-A12/MOSI1_26-A12/MOSI1") (pintype "bidirectional"))
      (node (ref "U3") (pin "3") (pinfunction "SDI_3") (pintype "bidirectional"))
      (node (ref "U4") (pin "3") (pinfunction "MOSI_3") (pintype "bidirectional"))
    )
    (net (code "56") (name "SPI1_SCLK") (class "Default")
      (node (ref "H1") (pin "2.1") (pinfunction "2.1_2.1") (pintype "bidirectional"))
      (node (ref "U$1") (pin "27-A13/SCK1") (pinfunction "27-A13/SCK1_27-A13/SCK1") (pintype "bidirectional"))
      (node (ref "U3") (pin "4") (pinfunction "SCK_4") (pintype "bidirectional"))
      (node (ref "U4") (pin "4") (pinfunction "SCK_4") (pintype "bidirectional"))
    )
    (net (code "57") (name "TX_ON") (class "Default")
      (node (ref "U$1") (pin "31-CTX3") (pinfunction "31-CTX3_31-CTX3") (pintype "bidirectional"))
      (node (ref "U3") (pin "11") (pinfunction "TXON_11") (pintype "bidirectional"))
    )
    (net (code "58") (name "T_CS") (class "Default")
      (node (ref "J4") (pin "1") (pinfunction "1_1") (pintype "passive"))
      (node (ref "U$1") (pin "10-CS\\MQSR") (pinfunction "10-CS/MQSR_10-CS\\MQSR") (pintype "bidirectional"))
    )
    (net (code "59") (name "T_CS1") (class "Default")
      (node (ref "H1") (pin "2.4") (pinfunction "2.4_2.4") (pintype "bidirectional"))
      (node (ref "U$1") (pin "9-OUT1C") (pinfunction "9-OUT1C_9-OUT1C") (pintype "bidirectional"))
    )
    (net (code "60") (name "T_GPIO2") (class "Default")
      (node (ref "J3") (pin "5") (pinfunction "5_5") (pintype "passive"))
      (node (ref "U$1") (pin "2-OUT2") (pinfunction "2-OUT2_2-OUT2") (pintype "bidirectional"))
    )
    (net (code "61") (name "T_GPIO3") (class "Default")
      (node (ref "J3") (pin "4") (pinfunction "4_4") (pintype "passive"))
      (node (ref "U$1") (pin "3-LRCLK2") (pinfunction "3-LRCLK2_3-LRCLK2") (pintype "bidirectional"))
    )
    (net (code "62") (name "T_GPIO4") (class "Default")
      (node (ref "J3") (pin "3") (pinfunction "3_3") (pintype "passive"))
      (node (ref "U$1") (pin "4-BCLK2") (pinfunction "4-BCLK2_4-BCLK2") (pintype "bidirectional"))
    )
    (net (code "63") (name "T_GPIO5") (class "Default")
      (node (ref "J3") (pin "2") (pinfunction "2_2") (pintype "passive"))
      (node (ref "U$1") (pin "5-IN2") (pinfunction "5-IN2_5-IN2") (pintype "bidirectional"))
    )
    (net (code "64") (name "T_GPIO6") (class "Default")
      (node (ref "J3") (pin "1") (pinfunction "1_1") (pintype "passive"))
      (node (ref "U$1") (pin "6-OUT1D") (pinfunction "6-OUT1D_6-OUT1D") (pintype "bidirectional"))
    )
    (net (code "65") (name "T_PROGRAM") (class "Default")
      (node (ref "J11") (pin "2") (pinfunction "2_2") (pintype "passive"))
      (node (ref "U$1") (pin "PROGRAM") (pinfunction "PROGRAM_PROGRAM") (pintype "bidirectional"))
    )
    (net (code "66") (name "T_VBAT") (class "Default")
      (node (ref "J11") (pin "1") (pinfunction "1_1") (pintype "passive"))
      (node (ref "U$1") (pin "VBAT") (pinfunction "VBAT_VBAT") (pintype "bidirectional"))
    )
    (net (code "67") (name "T_VUSB") (class "Default")
      (node (ref "J12") (pin "1") (pinfunction "1_1") (pintype "passive"))
      (node (ref "U$1") (pin "VUSB") (pinfunction "VUSB_VUSB") (pintype "bidirectional"))
    )
    (net (code "68") (name "UART2_RXD") (class "Default")
      (node (ref "J2") (pin "1") (pinfunction "1_1") (pintype "passive"))
      (node (ref "U$1") (pin "34-RX8") (pinfunction "34-RX8_34-RX8") (pintype "bidirectional"))
    )
    (net (code "69") (name "UART2_TXD") (class "Default")
      (node (ref "J2") (pin "3") (pinfunction "3_3") (pintype "passive"))
      (node (ref "U$1") (pin "35-TX8") (pinfunction "35/TX8_35-TX8") (pintype "bidirectional"))
    )
    (net (code "70") (name "UART4_RXD") (class "Default")
      (node (ref "H1") (pin "1.2") (pinfunction "1.2_1.2") (pintype "bidirectional"))
      (node (ref "U$1") (pin "0-RX1/CS1/CRX2") (pinfunction "0-RX1/CS1/CRX2_0-RX1/CS1/CRX2") (pintype "bidirectional"))
    )
    (net (code "71") (name "UART4_TXD") (class "Default")
      (node (ref "H1") (pin "1.1") (pinfunction "1.1_1.1") (pintype "bidirectional"))
      (node (ref "U$1") (pin "1-TX1/MISO1/CTX2") (pinfunction "1-TX1/MISO1/CTX2_1-TX1/MISO1/CTX2") (pintype "bidirectional"))
    )
    (net (code "72") (name "UART5_RXD") (class "Default")
      (node (ref "J14") (pin "3") (pinfunction "3_3") (pintype "passive"))
      (node (ref "U$1") (pin "29-TX7") (pinfunction "29-TX7_29-TX7") (pintype "bidirectional"))
      (node (ref "U6") (pin "42") (pinfunction "GPS_RXDO_42") (pintype "input"))
    )
    (net (code "73") (name "UART5_TXD") (class "Default")
      (node (ref "J14") (pin "4") (pinfunction "4_4") (pintype "passive"))
      (node (ref "U$1") (pin "28-RX7") (pinfunction "28-RX7_28-RX7") (pintype "bidirectional"))
      (node (ref "U6") (pin "44") (pinfunction "GPS_TXD0_44") (pintype "output"))
    )
    (net (code "74") (name "UART6_RX") (class "Default")
      (node (ref "U$1") (pin "7-RX2/OUT1A") (pinfunction "7-RX2/OUT1A_7-RX2/OUT1A") (pintype "bidirectional"))
      (node (ref "X1") (pin "8") (pinfunction "P$8_8") (pintype "bidirectional"))
    )
    (net (code "75") (name "UART6_TX") (class "Default")
      (node (ref "U$1") (pin "8-TX2/IN1") (pinfunction "8-TX2/IN1_8-TX2/IN1") (pintype "bidirectional"))
      (node (ref "X1") (pin "10") (pinfunction "P$10_10") (pintype "bidirectional"))
    )
    (net (code "76") (name "USB_DEV_D+") (class "Default")
      (node (ref "J12") (pin "4") (pinfunction "4_4") (pintype "passive"))
      (node (ref "U$1") (pin "D+") (pinfunction "D+_D+") (pintype "bidirectional"))
    )
    (net (code "77") (name "USB_DEV_D-") (class "Default")
      (node (ref "J12") (pin "3") (pinfunction "3_3") (pintype "passive"))
      (node (ref "U$1") (pin "D-") (pinfunction "D-_D-") (pintype "bidirectional"))
    )
    (net (code "78") (name "USB_HOST_D+") (class "Default")
      (node (ref "J13") (pin "1") (pinfunction "1_1") (pintype "passive"))
      (node (ref "U$1") (pin "DP") (pinfunction "DP_DP") (pintype "bidirectional"))
    )
    (net (code "79") (name "USB_HOST_D-") (class "Default")
      (node (ref "J13") (pin "2") (pinfunction "2_2") (pintype "passive"))
      (node (ref "U$1") (pin "DM") (pinfunction "DM_DM") (pintype "bidirectional"))
    )
    (net (code "80") (name "unconnected-(H1-Pad1.9)") (class "Default")
      (node (ref "H1") (pin "1.9") (pinfunction "1.9_1.9") (pintype "bidirectional"))
    )
    (net (code "81") (name "unconnected-(H1-Pad1.10)") (class "Default")
      (node (ref "H1") (pin "1.10") (pinfunction "1.10_1.10") (pintype "bidirectional"))
    )
    (net (code "82") (name "unconnected-(H1-Pad1.11)") (class "Default")
      (node (ref "H1") (pin "1.11") (pinfunction "1.11_1.11") (pintype "bidirectional"))
    )
    (net (code "83") (name "unconnected-(H1-Pad1.12)") (class "Default")
      (node (ref "H1") (pin "1.12") (pinfunction "1.12_1.12") (pintype "bidirectional"))
    )
    (net (code "84") (name "unconnected-(H1-Pad1.13)") (class "Default")
      (node (ref "H1") (pin "1.13") (pinfunction "1.13_1.13") (pintype "bidirectional"))
    )
    (net (code "85") (name "unconnected-(H1-Pad1.14)") (class "Default")
      (node (ref "H1") (pin "1.14") (pinfunction "1.14_1.14") (pintype "bidirectional"))
    )
    (net (code "86") (name "unconnected-(H1-Pad1.15)") (class "Default")
      (node (ref "H1") (pin "1.15") (pinfunction "1.15_1.15") (pintype "bidirectional"))
    )
    (net (code "87") (name "unconnected-(H1-Pad1.16)") (class "Default")
      (node (ref "H1") (pin "1.16") (pinfunction "1.16_1.16") (pintype "bidirectional"))
    )
    (net (code "88") (name "unconnected-(H1-Pad1.17)") (class "Default")
      (node (ref "H1") (pin "1.17") (pinfunction "1.17_1.17") (pintype "bidirectional"))
    )
    (net (code "89") (name "unconnected-(H1-Pad1.18)") (class "Default")
      (node (ref "H1") (pin "1.18") (pinfunction "1.18_1.18") (pintype "bidirectional"))
    )
    (net (code "90") (name "unconnected-(H1-Pad1.19)") (class "Default")
      (node (ref "H1") (pin "1.19") (pinfunction "1.19_1.19") (pintype "bidirectional"))
    )
    (net (code "91") (name "unconnected-(H1-Pad1.20)") (class "Default")
      (node (ref "H1") (pin "1.20") (pinfunction "1.20_1.20") (pintype "bidirectional"))
    )
    (net (code "92") (name "unconnected-(H1-Pad1.21)") (class "Default")
      (node (ref "H1") (pin "1.21") (pinfunction "1.21_1.21") (pintype "bidirectional"))
    )
    (net (code "93") (name "unconnected-(H1-Pad1.22)") (class "Default")
      (node (ref "H1") (pin "1.22") (pinfunction "1.22_1.22") (pintype "bidirectional"))
    )
    (net (code "94") (name "unconnected-(H1-Pad1.23)") (class "Default")
      (node (ref "H1") (pin "1.23") (pinfunction "1.23_1.23") (pintype "bidirectional"))
    )
    (net (code "95") (name "unconnected-(H1-Pad1.24)") (class "Default")
      (node (ref "H1") (pin "1.24") (pinfunction "1.24_1.24") (pintype "bidirectional"))
    )
    (net (code "96") (name "unconnected-(H1-Pad1.25)") (class "Default")
      (node (ref "H1") (pin "1.25") (pinfunction "1.25_1.25") (pintype "bidirectional"))
    )
    (net (code "97") (name "unconnected-(H1-Pad1.26)") (class "Default")
      (node (ref "H1") (pin "1.26") (pinfunction "1.26_1.26") (pintype "bidirectional"))
    )
    (net (code "98") (name "unconnected-(H1-Pad1.27)") (class "Default")
      (node (ref "H1") (pin "1.27") (pinfunction "1.27_1.27") (pintype "bidirectional"))
    )
    (net (code "99") (name "unconnected-(H1-Pad1.28)") (class "Default")
      (node (ref "H1") (pin "1.28") (pinfunction "1.28_1.28") (pintype "bidirectional"))
    )
    (net (code "100") (name "unconnected-(H1-Pad1.29)") (class "Default")
      (node (ref "H1") (pin "1.29") (pinfunction "1.29_1.29") (pintype "bidirectional"))
    )
    (net (code "101") (name "unconnected-(H1-Pad1.30)") (class "Default")
      (node (ref "H1") (pin "1.30") (pinfunction "1.30_1.30") (pintype "bidirectional"))
    )
    (net (code "102") (name "unconnected-(H1-Pad1.31)") (class "Default")
      (node (ref "H1") (pin "1.31") (pinfunction "1.31_1.31") (pintype "bidirectional"))
    )
    (net (code "103") (name "unconnected-(H1-Pad1.32)") (class "Default")
      (node (ref "H1") (pin "1.32") (pinfunction "1.32_1.32") (pintype "bidirectional"))
    )
    (net (code "104") (name "unconnected-(H1-Pad1.33)") (class "Default")
      (node (ref "H1") (pin "1.33") (pinfunction "1.33_1.33") (pintype "bidirectional"))
    )
    (net (code "105") (name "unconnected-(H1-Pad1.34)") (class "Default")
      (node (ref "H1") (pin "1.34") (pinfunction "1.34_1.34") (pintype "bidirectional"))
    )
    (net (code "106") (name "unconnected-(H1-Pad1.35)") (class "Default")
      (node (ref "H1") (pin "1.35") (pinfunction "1.35_1.35") (pintype "bidirectional"))
    )
    (net (code "107") (name "unconnected-(H1-Pad1.36)") (class "Default")
      (node (ref "H1") (pin "1.36") (pinfunction "1.36_1.36") (pintype "bidirectional"))
    )
    (net (code "108") (name "unconnected-(H1-Pad1.37)") (class "Default")
      (node (ref "H1") (pin "1.37") (pinfunction "1.37_1.37") (pintype "bidirectional"))
    )
    (net (code "109") (name "unconnected-(H1-Pad1.38)") (class "Default")
      (node (ref "H1") (pin "1.38") (pinfunction "1.38_1.38") (pintype "bidirectional"))
    )
    (net (code "110") (name "unconnected-(H1-Pad1.39)") (class "Default")
      (node (ref "H1") (pin "1.39") (pinfunction "1.39_1.39") (pintype "bidirectional"))
    )
    (net (code "111") (name "unconnected-(H1-Pad1.40)") (class "Default")
      (node (ref "H1") (pin "1.40") (pinfunction "1.40_1.40") (pintype "bidirectional"))
    )
    (net (code "112") (name "unconnected-(H1-Pad1.42)") (class "Default")
      (node (ref "H1") (pin "1.42") (pinfunction "1.42_1.42") (pintype "bidirectional"))
    )
    (net (code "113") (name "unconnected-(H1-Pad1.44)") (class "Default")
      (node (ref "H1") (pin "1.44") (pinfunction "1.44_1.44") (pintype "bidirectional"))
    )
    (net (code "114") (name "unconnected-(H1-Pad1.45)") (class "Default")
      (node (ref "H1") (pin "1.45") (pinfunction "1.45_1.45") (pintype "bidirectional"))
    )
    (net (code "115") (name "unconnected-(H1-Pad1.46)") (class "Default")
      (node (ref "H1") (pin "1.46") (pinfunction "1.46_1.46") (pintype "bidirectional"))
    )
    (net (code "116") (name "unconnected-(H1-Pad1.47)") (class "Default")
      (node (ref "H1") (pin "1.47") (pinfunction "1.47_1.47") (pintype "bidirectional"))
    )
    (net (code "117") (name "unconnected-(H1-Pad1.48)") (class "Default")
      (node (ref "H1") (pin "1.48") (pinfunction "1.48_1.48") (pintype "bidirectional"))
    )
    (net (code "118") (name "unconnected-(H1-Pad1.49)") (class "Default")
      (node (ref "H1") (pin "1.49") (pinfunction "1.49_1.49") (pintype "bidirectional"))
    )
    (net (code "119") (name "unconnected-(H1-Pad1.50)") (class "Default")
      (node (ref "H1") (pin "1.50") (pinfunction "1.50_1.50") (pintype "bidirectional"))
    )
    (net (code "120") (name "unconnected-(H1-Pad1.51)") (class "Default")
      (node (ref "H1") (pin "1.51") (pinfunction "1.51_1.51") (pintype "bidirectional"))
    )
    (net (code "121") (name "unconnected-(H1-Pad1.52)") (class "Default")
      (node (ref "H1") (pin "1.52") (pinfunction "1.52_1.52") (pintype "bidirectional"))
    )
    (net (code "122") (name "unconnected-(H1-Pad2.5)") (class "Default")
      (node (ref "H1") (pin "2.5") (pinfunction "2.5_2.5") (pintype "bidirectional"))
    )
    (net (code "123") (name "unconnected-(H1-Pad2.6)") (class "Default")
      (node (ref "H1") (pin "2.6") (pinfunction "2.6_2.6") (pintype "bidirectional"))
    )
    (net (code "124") (name "unconnected-(H1-Pad2.8)") (class "Default")
      (node (ref "H1") (pin "2.8") (pinfunction "2.8_2.8") (pintype "bidirectional"))
    )
    (net (code "125") (name "unconnected-(H1-Pad2.9)") (class "Default")
      (node (ref "H1") (pin "2.9") (pinfunction "2.9_2.9") (pintype "bidirectional"))
    )
    (net (code "126") (name "unconnected-(H1-Pad2.10)") (class "Default")
      (node (ref "H1") (pin "2.10") (pinfunction "2.10_2.10") (pintype "bidirectional"))
    )
    (net (code "127") (name "unconnected-(H1-Pad2.11)") (class "Default")
      (node (ref "H1") (pin "2.11") (pinfunction "2.11_2.11") (pintype "bidirectional"))
    )
    (net (code "128") (name "unconnected-(H1-Pad2.12)") (class "Default")
      (node (ref "H1") (pin "2.12") (pinfunction "2.12_2.12") (pintype "bidirectional"))
    )
    (net (code "129") (name "unconnected-(H1-Pad2.13)") (class "Default")
      (node (ref "H1") (pin "2.13") (pinfunction "2.13_2.13") (pintype "bidirectional"))
    )
    (net (code "130") (name "unconnected-(H1-Pad2.15)") (class "Default")
      (node (ref "H1") (pin "2.15") (pinfunction "2.15_2.15") (pintype "bidirectional"))
    )
    (net (code "131") (name "unconnected-(H1-Pad2.16)") (class "Default")
      (node (ref "H1") (pin "2.16") (pinfunction "2.16_2.16") (pintype "bidirectional"))
    )
    (net (code "132") (name "unconnected-(H1-Pad2.18)") (class "Default")
      (node (ref "H1") (pin "2.18") (pinfunction "2.18_2.18") (pintype "bidirectional"))
    )
    (net (code "133") (name "unconnected-(H1-Pad2.19)") (class "Default")
      (node (ref "H1") (pin "2.19") (pinfunction "2.19_2.19") (pintype "bidirectional"))
    )
    (net (code "134") (name "unconnected-(H1-Pad2.20)") (class "Default")
      (node (ref "H1") (pin "2.20") (pinfunction "2.20_2.20") (pintype "bidirectional"))
    )
    (net (code "135") (name "unconnected-(H1-Pad2.23)") (class "Default")
      (node (ref "H1") (pin "2.23") (pinfunction "2.23_2.23") (pintype "bidirectional"))
    )
    (net (code "136") (name "unconnected-(H1-Pad2.24)") (class "Default")
      (node (ref "H1") (pin "2.24") (pinfunction "2.24_2.24") (pintype "bidirectional"))
    )
    (net (code "137") (name "unconnected-(H1-Pad2.31)") (class "Default")
      (node (ref "H1") (pin "2.31") (pinfunction "2.31_2.31") (pintype "bidirectional"))
    )
    (net (code "138") (name "unconnected-(H1-Pad2.33)") (class "Default")
      (node (ref "H1") (pin "2.33") (pinfunction "2.33_2.33") (pintype "bidirectional"))
    )
    (net (code "139") (name "unconnected-(H1-Pad2.34)") (class "Default")
      (node (ref "H1") (pin "2.34") (pinfunction "2.34_2.34") (pintype "bidirectional"))
    )
    (net (code "140") (name "unconnected-(H1-Pad2.35)") (class "Default")
      (node (ref "H1") (pin "2.35") (pinfunction "2.35_2.35") (pintype "bidirectional"))
    )
    (net (code "141") (name "unconnected-(H1-Pad2.36)") (class "Default")
      (node (ref "H1") (pin "2.36") (pinfunction "2.36_2.36") (pintype "bidirectional"))
    )
    (net (code "142") (name "unconnected-(H1-Pad2.37)") (class "Default")
      (node (ref "H1") (pin "2.37") (pinfunction "2.37_2.37") (pintype "bidirectional"))
    )
    (net (code "143") (name "unconnected-(H1-Pad2.38)") (class "Default")
      (node (ref "H1") (pin "2.38") (pinfunction "2.38_2.38") (pintype "bidirectional"))
    )
    (net (code "144") (name "unconnected-(H1-Pad2.39)") (class "Default")
      (node (ref "H1") (pin "2.39") (pinfunction "2.39_2.39") (pintype "bidirectional"))
    )
    (net (code "145") (name "unconnected-(H1-Pad2.40)") (class "Default")
      (node (ref "H1") (pin "2.40") (pinfunction "2.40_2.40") (pintype "bidirectional"))
    )
    (net (code "146") (name "unconnected-(H1-Pad2.41)") (class "Default")
      (node (ref "H1") (pin "2.41") (pinfunction "2.41_2.41") (pintype "bidirectional"))
    )
    (net (code "147") (name "unconnected-(H1-Pad2.42)") (class "Default")
      (node (ref "H1") (pin "2.42") (pinfunction "2.42_2.42") (pintype "bidirectional"))
    )
    (net (code "148") (name "unconnected-(H1-Pad2.43)") (class "Default")
      (node (ref "H1") (pin "2.43") (pinfunction "2.43_2.43") (pintype "bidirectional"))
    )
    (net (code "149") (name "unconnected-(H1-Pad2.44)") (class "Default")
      (node (ref "H1") (pin "2.44") (pinfunction "2.44_2.44") (pintype "bidirectional"))
    )
    (net (code "150") (name "unconnected-(H1-Pad2.45)") (class "Default")
      (node (ref "H1") (pin "2.45") (pinfunction "2.45_2.45") (pintype "bidirectional"))
    )
    (net (code "151") (name "unconnected-(H1-Pad2.46)") (class "Default")
      (node (ref "H1") (pin "2.46") (pinfunction "2.46_2.46") (pintype "bidirectional"))
    )
    (net (code "152") (name "unconnected-(H1-Pad2.49)") (class "Default")
      (node (ref "H1") (pin "2.49") (pinfunction "2.49_2.49") (pintype "bidirectional"))
    )
    (net (code "153") (name "unconnected-(H1-Pad2.50)") (class "Default")
      (node (ref "H1") (pin "2.50") (pinfunction "2.50_2.50") (pintype "bidirectional"))
    )
    (net (code "154") (name "unconnected-(H1-Pad2.51)") (class "Default")
      (node (ref "H1") (pin "2.51") (pinfunction "2.51_2.51") (pintype "bidirectional"))
    )
    (net (code "155") (name "unconnected-(H1-Pad2.52)") (class "Default")
      (node (ref "H1") (pin "2.52") (pinfunction "2.52_2.52") (pintype "bidirectional"))
    )
    (net (code "156") (name "unconnected-(H1-PadP$1)") (class "Default")
      (node (ref "H1") (pin "P$1") (pinfunction "P$1_P$1") (pintype "bidirectional"))
    )
    (net (code "157") (name "unconnected-(H1-PadP$2)") (class "Default")
      (node (ref "H1") (pin "P$2") (pinfunction "P$2_P$2") (pintype "bidirectional"))
    )
    (net (code "158") (name "unconnected-(H1-PadP$3)") (class "Default")
      (node (ref "H1") (pin "P$3") (pinfunction "P$3_P$3") (pintype "bidirectional"))
    )
    (net (code "159") (name "unconnected-(U$1-PadON{slash}OFF)") (class "Default")
      (node (ref "U$1") (pin "ON/OFF") (pinfunction "ON/OFF_ON/OFF") (pintype "bidirectional"))
    )
    (net (code "160") (name "unconnected-(U1-NC-Pad7)") (class "Default")
      (node (ref "U1") (pin "7") (pinfunction "NC_7") (pintype "no_connect"))
    )
    (net (code "161") (name "unconnected-(U1-NC_2-Pad2)") (class "Default")
      (node (ref "U1") (pin "2") (pinfunction "NC_2_2") (pintype "no_connect"))
    )
    (net (code "162") (name "unconnected-(U1-NC_3-Pad3)") (class "Default")
      (node (ref "U1") (pin "3") (pinfunction "NC_3_3") (pintype "no_connect"))
    )
    (net (code "163") (name "unconnected-(U1-NC_4-Pad6)") (class "Default")
      (node (ref "U1") (pin "6") (pinfunction "NC_4_6") (pintype "no_connect"))
    )
    (net (code "164") (name "unconnected-(U3-GPIO_2-Pad16)") (class "Default")
      (node (ref "U3") (pin "16") (pinfunction "GPIO_2_16") (pintype "bidirectional"))
    )
    (net (code "165") (name "unconnected-(U4-DIO0-Pad14)") (class "Default")
      (node (ref "U4") (pin "14") (pinfunction "DIO0_14") (pintype "bidirectional"))
    )
    (net (code "166") (name "unconnected-(U4-DIO2-Pad16)") (class "Default")
      (node (ref "U4") (pin "16") (pinfunction "DIO2_16") (pintype "bidirectional"))
    )
    (net (code "167") (name "unconnected-(U4-DIO3-Pad11)") (class "Default")
      (node (ref "U4") (pin "11") (pinfunction "DIO3_11") (pintype "bidirectional"))
    )
    (net (code "168") (name "unconnected-(U4-DIO4-Pad12)") (class "Default")
      (node (ref "U4") (pin "12") (pinfunction "DIO4_12") (pintype "bidirectional"))
    )
    (net (code "169") (name "unconnected-(U4-DIO5-Pad7)") (class "Default")
      (node (ref "U4") (pin "7") (pinfunction "DIO5_7") (pintype "bidirectional"))
    )
    (net (code "170") (name "unconnected-(U5-Pad1)") (class "Default")
      (node (ref "U5") (pin "1") (pinfunction "1_1") (pintype "passive"))
    )
    (net (code "171") (name "unconnected-(U6-P$3-Pad3)") (class "Default")
      (node (ref "U6") (pin "3") (pinfunction "P$3_3") (pintype "bidirectional"))
    )
    (net (code "172") (name "unconnected-(U6-P$4-Pad4)") (class "Default")
      (node (ref "U6") (pin "4") (pinfunction "P$4_4") (pintype "bidirectional"))
    )
    (net (code "173") (name "unconnected-(U6-P$5-Pad5)") (class "Default")
      (node (ref "U6") (pin "5") (pinfunction "P$5_5") (pintype "bidirectional"))
    )
    (net (code "174") (name "unconnected-(U6-P$6-Pad6)") (class "Default")
      (node (ref "U6") (pin "6") (pinfunction "P$6_6") (pintype "bidirectional"))
    )
    (net (code "175") (name "unconnected-(U6-P$8-Pad8)") (class "Default")
      (node (ref "U6") (pin "8") (pinfunction "P$8_8") (pintype "bidirectional"))
    )
    (net (code "176") (name "unconnected-(U6-P$12-Pad12)") (class "Default")
      (node (ref "U6") (pin "12") (pinfunction "P$12_12") (pintype "bidirectional"))
    )
    (net (code "177") (name "unconnected-(U6-P$13-Pad13)") (class "Default")
      (node (ref "U6") (pin "13") (pinfunction "P$13_13") (pintype "bidirectional"))
    )
    (net (code "178") (name "unconnected-(U6-P$14-Pad14)") (class "Default")
      (node (ref "U6") (pin "14") (pinfunction "P$14_14") (pintype "bidirectional"))
    )
    (net (code "179") (name "unconnected-(U6-P$16-Pad16)") (class "Default")
      (node (ref "U6") (pin "16") (pinfunction "P$16_16") (pintype "bidirectional"))
    )
    (net (code "180") (name "unconnected-(U6-P$17-Pad17)") (class "Default")
      (node (ref "U6") (pin "17") (pinfunction "P$17_17") (pintype "bidirectional"))
    )
    (net (code "181") (name "unconnected-(U6-P$20-Pad20)") (class "Default")
      (node (ref "U6") (pin "20") (pinfunction "P$20_20") (pintype "bidirectional"))
    )
    (net (code "182") (name "unconnected-(U6-P$23-Pad23)") (class "Default")
      (node (ref "U6") (pin "23") (pinfunction "P$23_23") (pintype "bidirectional"))
    )
    (net (code "183") (name "unconnected-(U6-P$26-Pad26)") (class "Default")
      (node (ref "U6") (pin "26") (pinfunction "P$26_26") (pintype "bidirectional"))
    )
    (net (code "184") (name "unconnected-(U6-P$30-Pad30)") (class "Default")
      (node (ref "U6") (pin "30") (pinfunction "P$30_30") (pintype "bidirectional"))
    )
    (net (code "185") (name "unconnected-(U6-P$34-Pad34)") (class "Default")
      (node (ref "U6") (pin "34") (pinfunction "P$34_34") (pintype "bidirectional"))
    )
    (net (code "186") (name "unconnected-(U6-P$35-Pad35)") (class "Default")
      (node (ref "U6") (pin "35") (pinfunction "P$35_35") (pintype "bidirectional"))
    )
    (net (code "187") (name "unconnected-(U6-P$36-Pad36)") (class "Default")
      (node (ref "U6") (pin "36") (pinfunction "P$36_36") (pintype "bidirectional"))
    )
    (net (code "188") (name "unconnected-(U6-P$37-Pad37)") (class "Default")
      (node (ref "U6") (pin "37") (pinfunction "P$37_37") (pintype "bidirectional"))
    )
    (net (code "189") (name "unconnected-(U6-P$38-Pad38)") (class "Default")
      (node (ref "U6") (pin "38") (pinfunction "P$38_38") (pintype "bidirectional"))
    )
    (net (code "190") (name "unconnected-(U6-P$39-Pad39)") (class "Default")
      (node (ref "U6") (pin "39") (pinfunction "P$39_39") (pintype "bidirectional"))
    )
    (net (code "191") (name "unconnected-(U6-P$40-Pad40)") (class "Default")
      (node (ref "U6") (pin "40") (pinfunction "P$40_40") (pintype "bidirectional"))
    )
    (net (code "192") (name "unconnected-(U6-P$41-Pad41)") (class "Default")
      (node (ref "U6") (pin "41") (pinfunction "P$41_41") (pintype "bidirectional"))
    )
    (net (code "193") (name "unconnected-(U6-P$43-Pad43)") (class "Default")
      (node (ref "U6") (pin "43") (pinfunction "P$43_43") (pintype "bidirectional"))
    )
    (net (code "194") (name "unconnected-(U6-P$45-Pad45)") (class "Default")
      (node (ref "U6") (pin "45") (pinfunction "P$45_45") (pintype "bidirectional"))
    )
    (net (code "195") (name "unconnected-(U6-P$46-Pad46)") (class "Default")
      (node (ref "U6") (pin "46") (pinfunction "P$46_46") (pintype "bidirectional"))
    )
    (net (code "196") (name "unconnected-(U6-P$47-Pad47)") (class "Default")
      (node (ref "U6") (pin "47") (pinfunction "P$47_47") (pintype "bidirectional"))
    )
    (net (code "197") (name "unconnected-(U6-P$48-Pad48)") (class "Default")
      (node (ref "U6") (pin "48") (pinfunction "P$48_48") (pintype "bidirectional"))
    )
    (net (code "198") (name "unconnected-(U6-P$49-Pad49)") (class "Default")
      (node (ref "U6") (pin "49") (pinfunction "P$49_49") (pintype "bidirectional"))
    )
    (net (code "199") (name "unconnected-(U6-P$50-Pad50)") (class "Default")
      (node (ref "U6") (pin "50") (pinfunction "P$50_50") (pintype "bidirectional"))
    )
    (net (code "200") (name "unconnected-(U6-P$51-Pad51)") (class "Default")
      (node (ref "U6") (pin "51") (pinfunction "P$51_51") (pintype "bidirectional"))
    )
    (net (code "201") (name "unconnected-(U6-P$52-Pad52)") (class "Default")
      (node (ref "U6") (pin "52") (pinfunction "P$52_52") (pintype "bidirectional"))
    )
    (net (code "202") (name "unconnected-(U6-P$53-Pad53)") (class "Default")
      (node (ref "U6") (pin "53") (pinfunction "P$53_53") (pintype "bidirectional"))
    )
    (net (code "203") (name "unconnected-(U6-P$54-Pad54)") (class "Default")
      (node (ref "U6") (pin "54") (pinfunction "P$54_54") (pintype "bidirectional"))
    )
    (net (code "204") (name "unconnected-(U6-P$55-Pad55)") (class "Default")
      (node (ref "U6") (pin "55") (pinfunction "P$55_55") (pintype "bidirectional"))
    )
    (net (code "205") (name "unconnected-(U6-P$56-Pad56)") (class "Default")
      (node (ref "U6") (pin "56") (pinfunction "P$56_56") (pintype "bidirectional"))
    )
    (net (code "206") (name "unconnected-(U6-P$57-Pad57)") (class "Default")
      (node (ref "U6") (pin "57") (pinfunction "P$57_57") (pintype "bidirectional"))
    )
    (net (code "207") (name "unconnected-(U6-P$59-Pad59)") (class "Default")
      (node (ref "U6") (pin "59") (pinfunction "P$59_59") (pintype "bidirectional"))
    )
    (net (code "208") (name "unconnected-(U6-P$60-Pad60)") (class "Default")
      (node (ref "U6") (pin "60") (pinfunction "P$60_60") (pintype "bidirectional"))
    )
    (net (code "209") (name "unconnected-(U6-P$61-Pad61)") (class "Default")
      (node (ref "U6") (pin "61") (pinfunction "P$61_61") (pintype "bidirectional"))
    )
    (net (code "210") (name "unconnected-(U6-P$62-Pad62)") (class "Default")
      (node (ref "U6") (pin "62") (pinfunction "P$62_62") (pintype "bidirectional"))
    )
    (net (code "211") (name "unconnected-(U6-P$63-Pad63)") (class "Default")
      (node (ref "U6") (pin "63") (pinfunction "P$63_63") (pintype "bidirectional"))
    )
    (net (code "212") (name "unconnected-(U6-P$65-Pad65)") (class "Default")
      (node (ref "U6") (pin "65") (pinfunction "P$65_65") (pintype "bidirectional"))
    )
    (net (code "213") (name "unconnected-(U6-P$66-Pad66)") (class "Default")
      (node (ref "U6") (pin "66") (pinfunction "P$66_66") (pintype "bidirectional"))
    )
    (net (code "214") (name "unconnected-(U6-P$67-Pad67)") (class "Default")
      (node (ref "U6") (pin "67") (pinfunction "P$67_67") (pintype "bidirectional"))
    )
    (net (code "215") (name "unconnected-(U6-P$68-Pad68)") (class "Default")
      (node (ref "U6") (pin "68") (pinfunction "P$68_68") (pintype "bidirectional"))
    )
    (net (code "216") (name "unconnected-(U6-P$69-Pad69)") (class "Default")
      (node (ref "U6") (pin "69") (pinfunction "P$69_69") (pintype "bidirectional"))
    )
    (net (code "217") (name "unconnected-(X1-P$1-Pad1)") (class "Default")
      (node (ref "X1") (pin "1") (pinfunction "P$1_1") (pintype "bidirectional"))
    )
    (net (code "218") (name "unconnected-(X1-P$4-Pad4)") (class "Default")
      (node (ref "X1") (pin "4") (pinfunction "P$4_4") (pintype "bidirectional"))
    )
    (net (code "219") (name "unconnected-(X1-P$6-Pad6)") (class "Default")
      (node (ref "X1") (pin "6") (pinfunction "P$6_6") (pintype "bidirectional"))
    )
    (net (code "220") (name "unconnected-(X1-P$7-Pad7)") (class "Default")
      (node (ref "X1") (pin "7") (pinfunction "P$7_7") (pintype "bidirectional"))
    )
    (net (code "221") (name "unconnected-(X1-P$9-Pad9)") (class "Default")
      (node (ref "X1") (pin "9") (pinfunction "P$9_9") (pintype "bidirectional"))
    )
    (net (code "222") (name "unconnected-(X1-P$12-Pad12)") (class "Default")
      (node (ref "X1") (pin "12") (pinfunction "P$12_12") (pintype "bidirectional"))
    )
    (net (code "223") (name "unconnected-(X1-P$14-Pad14)") (class "Default")
      (node (ref "X1") (pin "14") (pinfunction "P$14_14") (pintype "bidirectional"))
    )
    (net (code "224") (name "unconnected-(X1-P$17-Pad17)") (class "Default")
      (node (ref "X1") (pin "17") (pinfunction "P$17_17") (pintype "bidirectional"))
    )
    (net (code "225") (name "unconnected-(X1-P$20-Pad20)") (class "Default")
      (node (ref "X1") (pin "20") (pinfunction "P$20_20") (pintype "bidirectional"))
    )
    (net (code "226") (name "unconnected-(X1-P$25-Pad25)") (class "Default")
      (node (ref "X1") (pin "25") (pinfunction "P$25_25") (pintype "bidirectional"))
    )
    (net (code "227") (name "unconnected-(X1-P$27-Pad27)") (class "Default")
      (node (ref "X1") (pin "27") (pinfunction "P$27_27") (pintype "bidirectional"))
    )
    (net (code "228") (name "unconnected-(X1-P$28-Pad28)") (class "Default")
      (node (ref "X1") (pin "28") (pinfunction "P$28_28") (pintype "bidirectional"))
    )
    (net (code "229") (name "unconnected-(X1-P$29-Pad29)") (class "Default")
      (node (ref "X1") (pin "29") (pinfunction "P$29_29") (pintype "bidirectional"))
    )
    (net (code "230") (name "unconnected-(X1-P$30-Pad30)") (class "Default")
      (node (ref "X1") (pin "30") (pinfunction "P$30_30") (pintype "bidirectional"))
    )
    (net (code "231") (name "unconnected-(X1-P$31-Pad31)") (class "Default")
      (node (ref "X1") (pin "31") (pinfunction "P$31_31") (pintype "bidirectional"))
    )
    (net (code "232") (name "unconnected-(X1-P$32-Pad32)") (class "Default")
      (node (ref "X1") (pin "32") (pinfunction "P$32_32") (pintype "bidirectional"))
    )
    (net (code "233") (name "unconnected-(X1-P$33-Pad33)") (class "Default")
      (node (ref "X1") (pin "33") (pinfunction "P$33_33") (pintype "bidirectional"))
    )
    (net (code "234") (name "unconnected-(X1-P$34-Pad34)") (class "Default")
      (node (ref "X1") (pin "34") (pinfunction "P$34_34") (pintype "bidirectional"))
    )
    (net (code "235") (name "unconnected-(X1-P$35-Pad35)") (class "Default")
      (node (ref "X1") (pin "35") (pinfunction "P$35_35") (pintype "bidirectional"))
    )
    (net (code "236") (name "unconnected-(X1-P$36-Pad36)") (class "Default")
      (node (ref "X1") (pin "36") (pinfunction "P$36_36") (pintype "bidirectional"))
    )
    (net (code "237") (name "unconnected-(X1-P$37-Pad37)") (class "Default")
      (node (ref "X1") (pin "37") (pinfunction "P$37_37") (pintype "bidirectional"))
    )
    (net (code "238") (name "unconnected-(X1-P$38-Pad38)") (class "Default")
      (node (ref "X1") (pin "38") (pinfunction "P$38_38") (pintype "bidirectional"))
    )
    (net (code "239") (name "unconnected-(X1-P$40-Pad40)") (class "Default")
      (node (ref "X1") (pin "40") (pinfunction "P$40_40") (pintype "bidirectional"))
    )
    (net (code "240") (name "unconnected-(X2-Pad1)") (class "Default")
      (node (ref "X2") (pin "1") (pinfunction "1_1") (pintype "passive"))
    )
    (net (code "241") (name "unconnected-(X2AA-1-Pad33)") (class "Default")
      (node (ref "X2") (pin "33") (pinfunction "1_33") (pintype "passive"))
    )
    (net (code "242") (name "unconnected-(X2AB-1-Pad34)") (class "Default")
      (node (ref "X2") (pin "34") (pinfunction "1_34") (pintype "passive"))
    )
    (net (code "243") (name "unconnected-(X2AC-1-Pad35)") (class "Default")
      (node (ref "X2") (pin "35") (pinfunction "1_35") (pintype "passive"))
    )
    (net (code "244") (name "unconnected-(X2AD-1-Pad36)") (class "Default")
      (node (ref "X2") (pin "36") (pinfunction "1_36") (pintype "passive"))
    )
    (net (code "245") (name "unconnected-(X2AE-1-Pad37)") (class "Default")
      (node (ref "X2") (pin "37") (pinfunction "1_37") (pintype "passive"))
    )
    (net (code "246") (name "unconnected-(X2AF-1-Pad38)") (class "Default")
      (node (ref "X2") (pin "38") (pinfunction "1_38") (pintype "passive"))
    )
    (net (code "247") (name "unconnected-(X2AG-1-Pad39)") (class "Default")
      (node (ref "X2") (pin "39") (pinfunction "1_39") (pintype "passive"))
    )
    (net (code "248") (name "unconnected-(X2AH-1-Pad4)") (class "Default")
      (node (ref "X2") (pin "4") (pinfunction "1_4") (pintype "passive"))
    )
    (net (code "249") (name "unconnected-(X2AI-1-Pad40)") (class "Default")
      (node (ref "X2") (pin "40") (pinfunction "1_40") (pintype "passive"))
    )
    (net (code "250") (name "unconnected-(X2AJ-1-Pad5)") (class "Default")
      (node (ref "X2") (pin "5") (pinfunction "1_5") (pintype "passive"))
    )
    (net (code "251") (name "unconnected-(X2AK-1-Pad6)") (class "Default")
      (node (ref "X2") (pin "6") (pinfunction "1_6") (pintype "passive"))
    )
    (net (code "252") (name "unconnected-(X2AL-1-Pad7)") (class "Default")
      (node (ref "X2") (pin "7") (pinfunction "1_7") (pintype "passive"))
    )
    (net (code "253") (name "unconnected-(X2AM-1-Pad8)") (class "Default")
      (node (ref "X2") (pin "8") (pinfunction "1_8") (pintype "passive"))
    )
    (net (code "254") (name "unconnected-(X2AN-1-Pad9)") (class "Default")
      (node (ref "X2") (pin "9") (pinfunction "1_9") (pintype "passive"))
    )
    (net (code "255") (name "unconnected-(X2B-1-Pad10)") (class "Default")
      (node (ref "X2") (pin "10") (pinfunction "1_10") (pintype "passive"))
    )
    (net (code "256") (name "unconnected-(X2C-1-Pad11)") (class "Default")
      (node (ref "X2") (pin "11") (pinfunction "1_11") (pintype "passive"))
    )
    (net (code "257") (name "unconnected-(X2D-1-Pad12)") (class "Default")
      (node (ref "X2") (pin "12") (pinfunction "1_12") (pintype "passive"))
    )
    (net (code "258") (name "unconnected-(X2E-1-Pad13)") (class "Default")
      (node (ref "X2") (pin "13") (pinfunction "1_13") (pintype "passive"))
    )
    (net (code "259") (name "unconnected-(X2F-1-Pad14)") (class "Default")
      (node (ref "X2") (pin "14") (pinfunction "1_14") (pintype "passive"))
    )
    (net (code "260") (name "unconnected-(X2G-1-Pad15)") (class "Default")
      (node (ref "X2") (pin "15") (pinfunction "1_15") (pintype "passive"))
    )
    (net (code "261") (name "unconnected-(X2H-1-Pad16)") (class "Default")
      (node (ref "X2") (pin "16") (pinfunction "1_16") (pintype "passive"))
    )
    (net (code "262") (name "unconnected-(X2I-1-Pad17)") (class "Default")
      (node (ref "X2") (pin "17") (pinfunction "1_17") (pintype "passive"))
    )
    (net (code "263") (name "unconnected-(X2J-1-Pad18)") (class "Default")
      (node (ref "X2") (pin "18") (pinfunction "1_18") (pintype "passive"))
    )
    (net (code "264") (name "unconnected-(X2K-1-Pad19)") (class "Default")
      (node (ref "X2") (pin "19") (pinfunction "1_19") (pintype "passive"))
    )
    (net (code "265") (name "unconnected-(X2L-1-Pad2)") (class "Default")
      (node (ref "X2") (pin "2") (pinfunction "1_2") (pintype "passive"))
    )
    (net (code "266") (name "unconnected-(X2M-1-Pad20)") (class "Default")
      (node (ref "X2") (pin "20") (pinfunction "1_20") (pintype "passive"))
    )
    (net (code "267") (name "unconnected-(X2N-1-Pad21)") (class "Default")
      (node (ref "X2") (pin "21") (pinfunction "1_21") (pintype "passive"))
    )
    (net (code "268") (name "unconnected-(X2O-1-Pad22)") (class "Default")
      (node (ref "X2") (pin "22") (pinfunction "1_22") (pintype "passive"))
    )
    (net (code "269") (name "unconnected-(X2P-1-Pad23)") (class "Default")
      (node (ref "X2") (pin "23") (pinfunction "1_23") (pintype "passive"))
    )
    (net (code "270") (name "unconnected-(X2Q-1-Pad24)") (class "Default")
      (node (ref "X2") (pin "24") (pinfunction "1_24") (pintype "passive"))
    )
    (net (code "271") (name "unconnected-(X2R-1-Pad25)") (class "Default")
      (node (ref "X2") (pin "25") (pinfunction "1_25") (pintype "passive"))
    )
    (net (code "272") (name "unconnected-(X2S-1-Pad26)") (class "Default")
      (node (ref "X2") (pin "26") (pinfunction "1_26") (pintype "passive"))
    )
    (net (code "273") (name "unconnected-(X2T-1-Pad27)") (class "Default")
      (node (ref "X2") (pin "27") (pinfunction "1_27") (pintype "passive"))
    )
    (net (code "274") (name "unconnected-(X2U-1-Pad28)") (class "Default")
      (node (ref "X2") (pin "28") (pinfunction "1_28") (pintype "passive"))
    )
    (net (code "275") (name "unconnected-(X2V-1-Pad29)") (class "Default")
      (node (ref "X2") (pin "29") (pinfunction "1_29") (pintype "passive"))
    )
    (net (code "276") (name "unconnected-(X2W-1-Pad3)") (class "Default")
      (node (ref "X2") (pin "3") (pinfunction "1_3") (pintype "passive"))
    )
    (net (code "277") (name "unconnected-(X2X-1-Pad30)") (class "Default")
      (node (ref "X2") (pin "30") (pinfunction "1_30") (pintype "passive"))
    )
    (net (code "278") (name "unconnected-(X2Y-1-Pad31)") (class "Default")
      (node (ref "X2") (pin "31") (pinfunction "1_31") (pintype "passive"))
    )
    (net (code "279") (name "unconnected-(X2Z-1-Pad32)") (class "Default")
      (node (ref "X2") (pin "32") (pinfunction "1_32") (pintype "passive"))
    )
  )
)
